# core.net
KiCad netlist of a schematic drawn in EAGLE
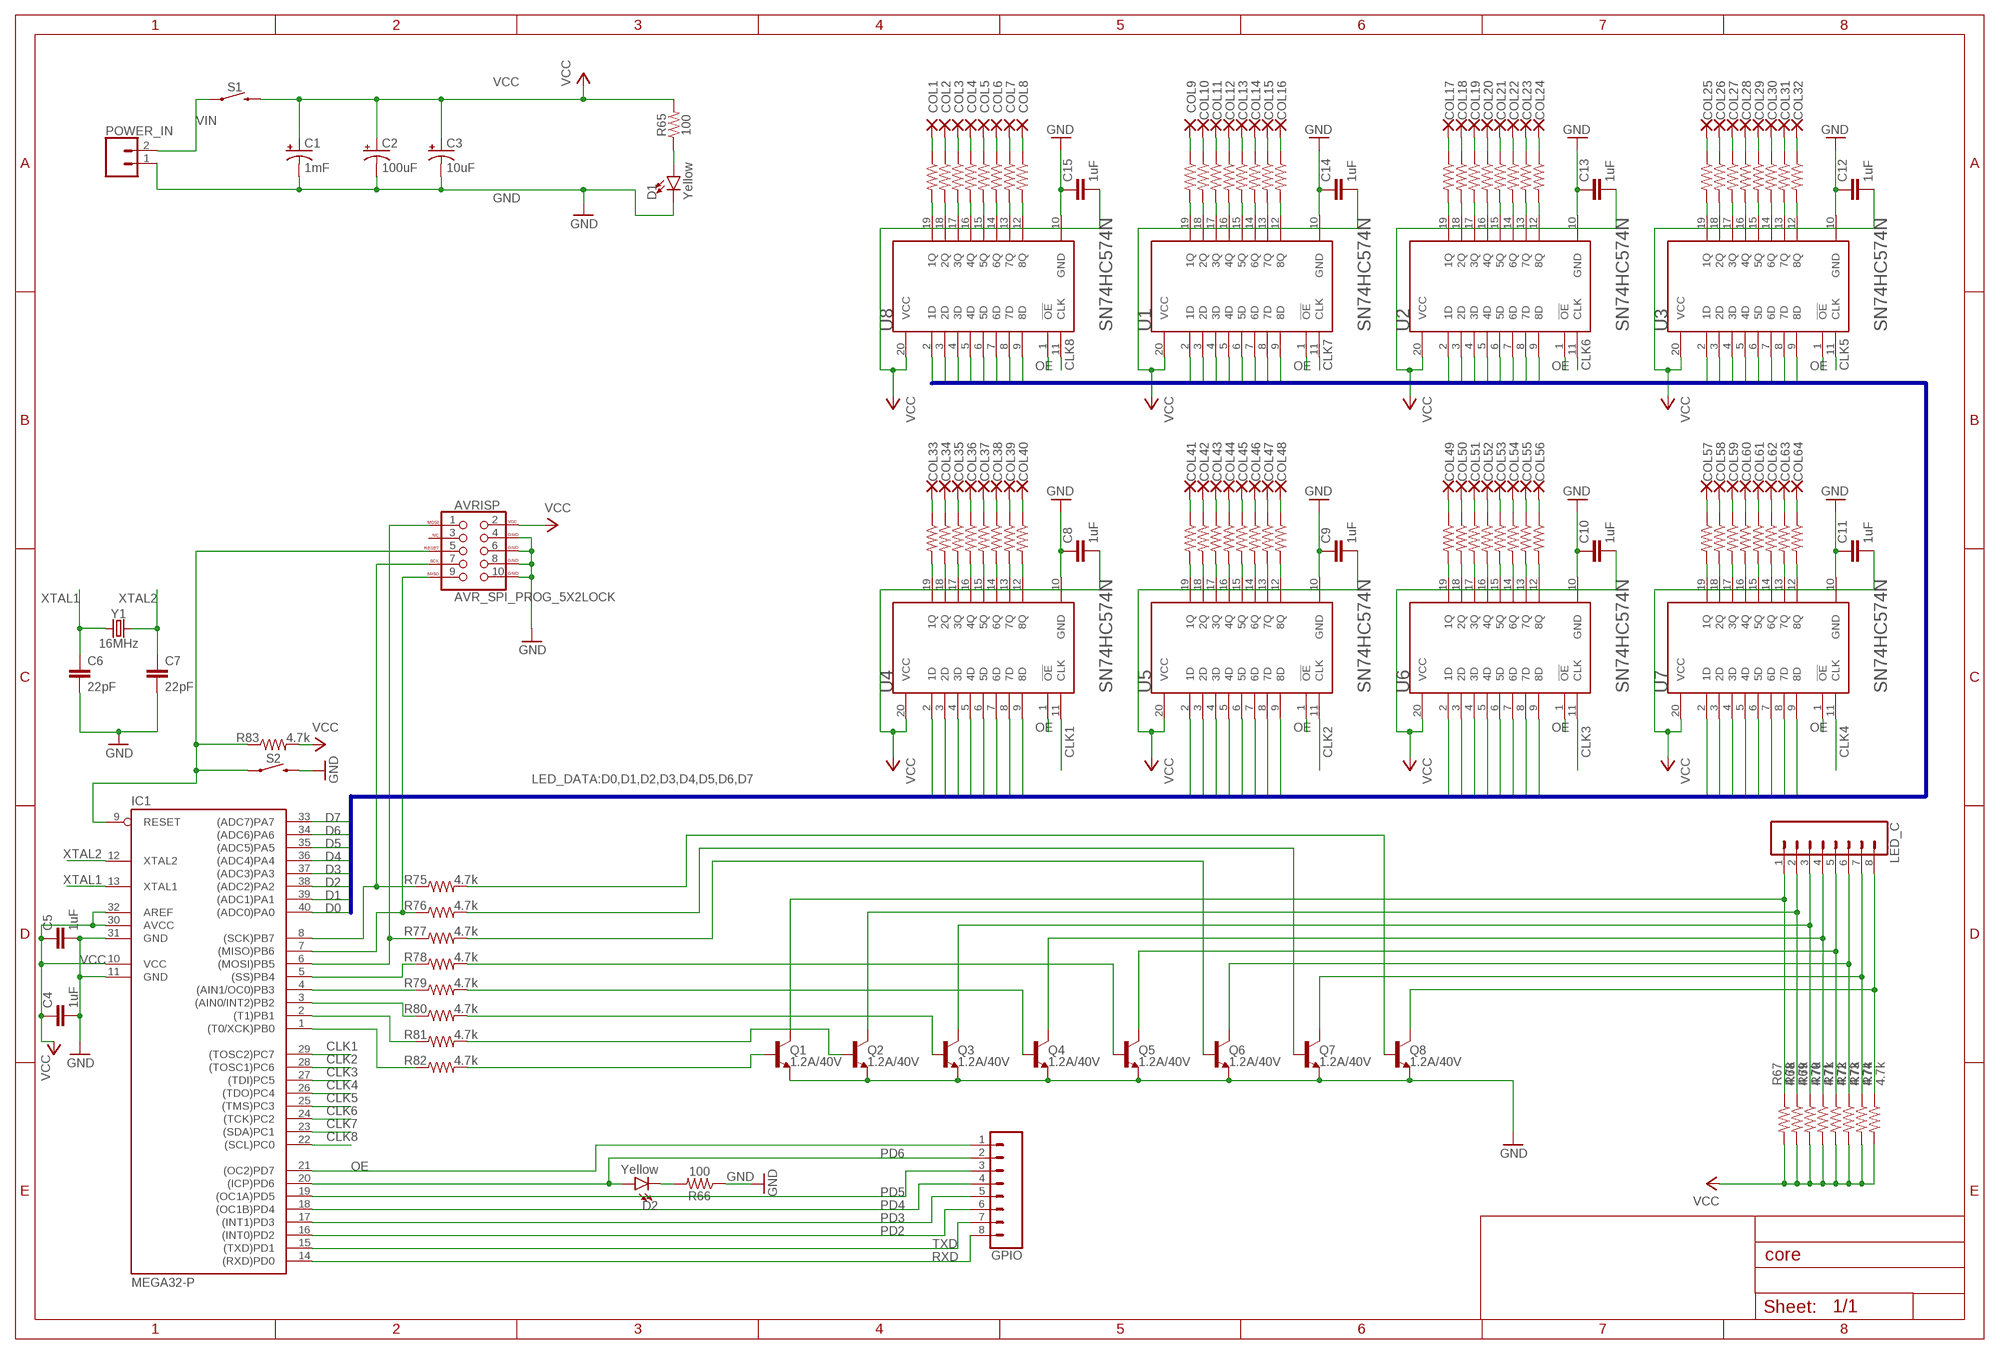
[diagram p0: schematic, sheet 1]

(export (version "E")
  (design (tool "Eeschema 10.0.6"))
  (components
    (comp (ref "AVRISP")
      (value "AVR_SPI_PROG_5X2LOCK")
      (footprint "eagle-import:2X5-SHROUDED_LOCK")
      (libsource (lib "eagle-import") (part "AVR_SPI_PROG_5X2LOCK"))
    )
    (comp (ref "C1")
      (value "1mF")
      (footprint "eagle-import:CPOL-RADIAL-5MM-10MM")
      (libsource (lib "eagle-import") (part "1000UF-RADIAL-5MM-25V-20%"))
    )
    (comp (ref "C2")
      (value "100uF")
      (footprint "eagle-import:CPOL-RADIAL-2.5MM-6.5MM")
      (libsource (lib "eagle-import") (part "100UF-POLAR-RADIAL-2.5MM-25V-20%"))
    )
    (comp (ref "C3")
      (value "10uF")
      (footprint "eagle-import:CPOL-RADIAL-2.5MM-5MM")
      (libsource (lib "eagle-import") (part "10UF-POLAR-RADIAL-2.5MM-25V-20%"))
    )
    (comp (ref "C4")
      (value "1uF")
      (footprint "eagle-import:C2.5-3")
      (libsource (lib "eagle-import") (part "C2,5-3"))
    )
    (comp (ref "C5")
      (value "1uF")
      (footprint "eagle-import:C2.5-3")
      (libsource (lib "eagle-import") (part "C2,5-3"))
    )
    (comp (ref "C6")
      (value "22pF")
      (footprint "eagle-import:CAP-PTH-2.54")
      (libsource (lib "eagle-import") (part "22PF-PTH-2.54MM-200V-5%"))
    )
    (comp (ref "C7")
      (value "22pF")
      (footprint "eagle-import:CAP-PTH-2.54")
      (libsource (lib "eagle-import") (part "22PF-PTH-2.54MM-200V-5%"))
    )
    (comp (ref "C8")
      (value "1uF")
      (footprint "eagle-import:C2.5-3")
      (libsource (lib "eagle-import") (part "C2,5-3"))
    )
    (comp (ref "C9")
      (value "1uF")
      (footprint "eagle-import:C2.5-3")
      (libsource (lib "eagle-import") (part "C2,5-3"))
    )
    (comp (ref "C10")
      (value "1uF")
      (footprint "eagle-import:C2.5-3")
      (libsource (lib "eagle-import") (part "C2,5-3"))
    )
    (comp (ref "C11")
      (value "1uF")
      (footprint "eagle-import:C2.5-3")
      (libsource (lib "eagle-import") (part "C2,5-3"))
    )
    (comp (ref "C12")
      (value "1uF")
      (footprint "eagle-import:C2.5-3")
      (libsource (lib "eagle-import") (part "C2,5-3"))
    )
    (comp (ref "C13")
      (value "1uF")
      (footprint "eagle-import:C2.5-3")
      (libsource (lib "eagle-import") (part "C2,5-3"))
    )
    (comp (ref "C14")
      (value "1uF")
      (footprint "eagle-import:C2.5-3")
      (libsource (lib "eagle-import") (part "C2,5-3"))
    )
    (comp (ref "C15")
      (value "1uF")
      (footprint "eagle-import:C2.5-3")
      (libsource (lib "eagle-import") (part "C2,5-3"))
    )
    (comp (ref "COL1")
      (value "1,6/0,9")
      (footprint "eagle-import:1,6_0,9")
      (libsource (lib "eagle-import") (part "1,6/0,9"))
    )
    (comp (ref "COL2")
      (value "1,6/0,9")
      (footprint "eagle-import:1,6_0,9")
      (libsource (lib "eagle-import") (part "1,6/0,9"))
    )
    (comp (ref "COL3")
      (value "1,6/0,9")
      (footprint "eagle-import:1,6_0,9")
      (libsource (lib "eagle-import") (part "1,6/0,9"))
    )
    (comp (ref "COL4")
      (value "1,6/0,9")
      (footprint "eagle-import:1,6_0,9")
      (libsource (lib "eagle-import") (part "1,6/0,9"))
    )
    (comp (ref "COL5")
      (value "1,6/0,9")
      (footprint "eagle-import:1,6_0,9")
      (libsource (lib "eagle-import") (part "1,6/0,9"))
    )
    (comp (ref "COL6")
      (value "1,6/0,9")
      (footprint "eagle-import:1,6_0,9")
      (libsource (lib "eagle-import") (part "1,6/0,9"))
    )
    (comp (ref "COL7")
      (value "1,6/0,9")
      (footprint "eagle-import:1,6_0,9")
      (libsource (lib "eagle-import") (part "1,6/0,9"))
    )
    (comp (ref "COL8")
      (value "1,6/0,9")
      (footprint "eagle-import:1,6_0,9")
      (libsource (lib "eagle-import") (part "1,6/0,9"))
    )
    (comp (ref "COL9")
      (value "1,6/0,9")
      (footprint "eagle-import:1,6_0,9")
      (libsource (lib "eagle-import") (part "1,6/0,9"))
    )
    (comp (ref "COL10")
      (value "1,6/0,9")
      (footprint "eagle-import:1,6_0,9")
      (libsource (lib "eagle-import") (part "1,6/0,9"))
    )
    (comp (ref "COL11")
      (value "1,6/0,9")
      (footprint "eagle-import:1,6_0,9")
      (libsource (lib "eagle-import") (part "1,6/0,9"))
    )
    (comp (ref "COL12")
      (value "1,6/0,9")
      (footprint "eagle-import:1,6_0,9")
      (libsource (lib "eagle-import") (part "1,6/0,9"))
    )
    (comp (ref "COL13")
      (value "1,6/0,9")
      (footprint "eagle-import:1,6_0,9")
      (libsource (lib "eagle-import") (part "1,6/0,9"))
    )
    (comp (ref "COL14")
      (value "1,6/0,9")
      (footprint "eagle-import:1,6_0,9")
      (libsource (lib "eagle-import") (part "1,6/0,9"))
    )
    (comp (ref "COL15")
      (value "1,6/0,9")
      (footprint "eagle-import:1,6_0,9")
      (libsource (lib "eagle-import") (part "1,6/0,9"))
    )
    (comp (ref "COL16")
      (value "1,6/0,9")
      (footprint "eagle-import:1,6_0,9")
      (libsource (lib "eagle-import") (part "1,6/0,9"))
    )
    (comp (ref "COL17")
      (value "1,6/0,9")
      (footprint "eagle-import:1,6_0,9")
      (libsource (lib "eagle-import") (part "1,6/0,9"))
    )
    (comp (ref "COL18")
      (value "1,6/0,9")
      (footprint "eagle-import:1,6_0,9")
      (libsource (lib "eagle-import") (part "1,6/0,9"))
    )
    (comp (ref "COL19")
      (value "1,6/0,9")
      (footprint "eagle-import:1,6_0,9")
      (libsource (lib "eagle-import") (part "1,6/0,9"))
    )
    (comp (ref "COL20")
      (value "1,6/0,9")
      (footprint "eagle-import:1,6_0,9")
      (libsource (lib "eagle-import") (part "1,6/0,9"))
    )
    (comp (ref "COL21")
      (value "1,6/0,9")
      (footprint "eagle-import:1,6_0,9")
      (libsource (lib "eagle-import") (part "1,6/0,9"))
    )
    (comp (ref "COL22")
      (value "1,6/0,9")
      (footprint "eagle-import:1,6_0,9")
      (libsource (lib "eagle-import") (part "1,6/0,9"))
    )
    (comp (ref "COL23")
      (value "1,6/0,9")
      (footprint "eagle-import:1,6_0,9")
      (libsource (lib "eagle-import") (part "1,6/0,9"))
    )
    (comp (ref "COL24")
      (value "1,6/0,9")
      (footprint "eagle-import:1,6_0,9")
      (libsource (lib "eagle-import") (part "1,6/0,9"))
    )
    (comp (ref "COL25")
      (value "1,6/0,9")
      (footprint "eagle-import:1,6_0,9")
      (libsource (lib "eagle-import") (part "1,6/0,9"))
    )
    (comp (ref "COL26")
      (value "1,6/0,9")
      (footprint "eagle-import:1,6_0,9")
      (libsource (lib "eagle-import") (part "1,6/0,9"))
    )
    (comp (ref "COL27")
      (value "1,6/0,9")
      (footprint "eagle-import:1,6_0,9")
      (libsource (lib "eagle-import") (part "1,6/0,9"))
    )
    (comp (ref "COL28")
      (value "1,6/0,9")
      (footprint "eagle-import:1,6_0,9")
      (libsource (lib "eagle-import") (part "1,6/0,9"))
    )
    (comp (ref "COL29")
      (value "1,6/0,9")
      (footprint "eagle-import:1,6_0,9")
      (libsource (lib "eagle-import") (part "1,6/0,9"))
    )
    (comp (ref "COL30")
      (value "1,6/0,9")
      (footprint "eagle-import:1,6_0,9")
      (libsource (lib "eagle-import") (part "1,6/0,9"))
    )
    (comp (ref "COL31")
      (value "1,6/0,9")
      (footprint "eagle-import:1,6_0,9")
      (libsource (lib "eagle-import") (part "1,6/0,9"))
    )
    (comp (ref "COL32")
      (value "1,6/0,9")
      (footprint "eagle-import:1,6_0,9")
      (libsource (lib "eagle-import") (part "1,6/0,9"))
    )
    (comp (ref "COL33")
      (value "1,6/0,9")
      (footprint "eagle-import:1,6_0,9")
      (libsource (lib "eagle-import") (part "1,6/0,9"))
    )
    (comp (ref "COL34")
      (value "1,6/0,9")
      (footprint "eagle-import:1,6_0,9")
      (libsource (lib "eagle-import") (part "1,6/0,9"))
    )
    (comp (ref "COL35")
      (value "1,6/0,9")
      (footprint "eagle-import:1,6_0,9")
      (libsource (lib "eagle-import") (part "1,6/0,9"))
    )
    (comp (ref "COL36")
      (value "1,6/0,9")
      (footprint "eagle-import:1,6_0,9")
      (libsource (lib "eagle-import") (part "1,6/0,9"))
    )
    (comp (ref "COL37")
      (value "1,6/0,9")
      (footprint "eagle-import:1,6_0,9")
      (libsource (lib "eagle-import") (part "1,6/0,9"))
    )
    (comp (ref "COL38")
      (value "1,6/0,9")
      (footprint "eagle-import:1,6_0,9")
      (libsource (lib "eagle-import") (part "1,6/0,9"))
    )
    (comp (ref "COL39")
      (value "1,6/0,9")
      (footprint "eagle-import:1,6_0,9")
      (libsource (lib "eagle-import") (part "1,6/0,9"))
    )
    (comp (ref "COL40")
      (value "1,6/0,9")
      (footprint "eagle-import:1,6_0,9")
      (libsource (lib "eagle-import") (part "1,6/0,9"))
    )
    (comp (ref "COL41")
      (value "1,6/0,9")
      (footprint "eagle-import:1,6_0,9")
      (libsource (lib "eagle-import") (part "1,6/0,9"))
    )
    (comp (ref "COL42")
      (value "1,6/0,9")
      (footprint "eagle-import:1,6_0,9")
      (libsource (lib "eagle-import") (part "1,6/0,9"))
    )
    (comp (ref "COL43")
      (value "1,6/0,9")
      (footprint "eagle-import:1,6_0,9")
      (libsource (lib "eagle-import") (part "1,6/0,9"))
    )
    (comp (ref "COL44")
      (value "1,6/0,9")
      (footprint "eagle-import:1,6_0,9")
      (libsource (lib "eagle-import") (part "1,6/0,9"))
    )
    (comp (ref "COL45")
      (value "1,6/0,9")
      (footprint "eagle-import:1,6_0,9")
      (libsource (lib "eagle-import") (part "1,6/0,9"))
    )
    (comp (ref "COL46")
      (value "1,6/0,9")
      (footprint "eagle-import:1,6_0,9")
      (libsource (lib "eagle-import") (part "1,6/0,9"))
    )
    (comp (ref "COL47")
      (value "1,6/0,9")
      (footprint "eagle-import:1,6_0,9")
      (libsource (lib "eagle-import") (part "1,6/0,9"))
    )
    (comp (ref "COL48")
      (value "1,6/0,9")
      (footprint "eagle-import:1,6_0,9")
      (libsource (lib "eagle-import") (part "1,6/0,9"))
    )
    (comp (ref "COL49")
      (value "1,6/0,9")
      (footprint "eagle-import:1,6_0,9")
      (libsource (lib "eagle-import") (part "1,6/0,9"))
    )
    (comp (ref "COL50")
      (value "1,6/0,9")
      (footprint "eagle-import:1,6_0,9")
      (libsource (lib "eagle-import") (part "1,6/0,9"))
    )
    (comp (ref "COL51")
      (value "1,6/0,9")
      (footprint "eagle-import:1,6_0,9")
      (libsource (lib "eagle-import") (part "1,6/0,9"))
    )
    (comp (ref "COL52")
      (value "1,6/0,9")
      (footprint "eagle-import:1,6_0,9")
      (libsource (lib "eagle-import") (part "1,6/0,9"))
    )
    (comp (ref "COL53")
      (value "1,6/0,9")
      (footprint "eagle-import:1,6_0,9")
      (libsource (lib "eagle-import") (part "1,6/0,9"))
    )
    (comp (ref "COL54")
      (value "1,6/0,9")
      (footprint "eagle-import:1,6_0,9")
      (libsource (lib "eagle-import") (part "1,6/0,9"))
    )
    (comp (ref "COL55")
      (value "1,6/0,9")
      (footprint "eagle-import:1,6_0,9")
      (libsource (lib "eagle-import") (part "1,6/0,9"))
    )
    (comp (ref "COL56")
      (value "1,6/0,9")
      (footprint "eagle-import:1,6_0,9")
      (libsource (lib "eagle-import") (part "1,6/0,9"))
    )
    (comp (ref "COL57")
      (value "1,6/0,9")
      (footprint "eagle-import:1,6_0,9")
      (libsource (lib "eagle-import") (part "1,6/0,9"))
    )
    (comp (ref "COL58")
      (value "1,6/0,9")
      (footprint "eagle-import:1,6_0,9")
      (libsource (lib "eagle-import") (part "1,6/0,9"))
    )
    (comp (ref "COL59")
      (value "1,6/0,9")
      (footprint "eagle-import:1,6_0,9")
      (libsource (lib "eagle-import") (part "1,6/0,9"))
    )
    (comp (ref "COL60")
      (value "1,6/0,9")
      (footprint "eagle-import:1,6_0,9")
      (libsource (lib "eagle-import") (part "1,6/0,9"))
    )
    (comp (ref "COL61")
      (value "1,6/0,9")
      (footprint "eagle-import:1,6_0,9")
      (libsource (lib "eagle-import") (part "1,6/0,9"))
    )
    (comp (ref "COL62")
      (value "1,6/0,9")
      (footprint "eagle-import:1,6_0,9")
      (libsource (lib "eagle-import") (part "1,6/0,9"))
    )
    (comp (ref "COL63")
      (value "1,6/0,9")
      (footprint "eagle-import:1,6_0,9")
      (libsource (lib "eagle-import") (part "1,6/0,9"))
    )
    (comp (ref "COL64")
      (value "1,6/0,9")
      (footprint "eagle-import:1,6_0,9")
      (libsource (lib "eagle-import") (part "1,6/0,9"))
    )
    (comp (ref "D1")
      (value "Yellow")
      (footprint "eagle-import:LED-1206")
      (libsource (lib "eagle-import") (part "LED-YELLOWLILYPAD"))
    )
    (comp (ref "D2")
      (value "Yellow")
      (footprint "eagle-import:LED-1206")
      (libsource (lib "eagle-import") (part "LED-YELLOWLILYPAD"))
    )
    (comp (ref "GPIO")
      (value "CONN_08\"")
      (footprint "eagle-import:1X08")
      (libsource (lib "eagle-import") (part "CONN_08{dblquote}"))
    )
    (comp (ref "IC1")
      (value "MEGA32-P")
      (footprint "eagle-import:DIL40")
      (fields (field (name "MPN") "ATMEGA32-16PU"))
      (libsource (lib "eagle-import") (part "MEGA32-P"))
    )
    (comp (ref "LED_C")
      (value "CONN_08\"")
      (footprint "eagle-import:1X08")
      (libsource (lib "eagle-import") (part "CONN_08{dblquote}"))
    )
    (comp (ref "POWER_IN")
      (value "CONN_02POLAR")
      (footprint "eagle-import:MOLEX-1X2")
      (libsource (lib "eagle-import") (part "CONN_02POLAR"))
    )
    (comp (ref "Q1")
      (value "1.2A/40V")
      (footprint "eagle-import:SOT23-3")
      (libsource (lib "eagle-import") (part "TRANS_NPN-MMBT2222AL"))
    )
    (comp (ref "Q2")
      (value "1.2A/40V")
      (footprint "eagle-import:SOT23-3")
      (libsource (lib "eagle-import") (part "TRANS_NPN-MMBT2222AL"))
    )
    (comp (ref "Q3")
      (value "1.2A/40V")
      (footprint "eagle-import:SOT23-3")
      (libsource (lib "eagle-import") (part "TRANS_NPN-MMBT2222AL"))
    )
    (comp (ref "Q4")
      (value "1.2A/40V")
      (footprint "eagle-import:SOT23-3")
      (libsource (lib "eagle-import") (part "TRANS_NPN-MMBT2222AL"))
    )
    (comp (ref "Q5")
      (value "1.2A/40V")
      (footprint "eagle-import:SOT23-3")
      (libsource (lib "eagle-import") (part "TRANS_NPN-MMBT2222AL"))
    )
    (comp (ref "Q6")
      (value "1.2A/40V")
      (footprint "eagle-import:SOT23-3")
      (libsource (lib "eagle-import") (part "TRANS_NPN-MMBT2222AL"))
    )
    (comp (ref "Q7")
      (value "1.2A/40V")
      (footprint "eagle-import:SOT23-3")
      (libsource (lib "eagle-import") (part "TRANS_NPN-MMBT2222AL"))
    )
    (comp (ref "Q8")
      (value "1.2A/40V")
      (footprint "eagle-import:SOT23-3")
      (libsource (lib "eagle-import") (part "TRANS_NPN-MMBT2222AL"))
    )
    (comp (ref "R1")
      (value "100")
      (footprint "eagle-import:AXIAL-0.3")
      (libsource (lib "eagle-import") (part "100OHM-HORIZ-1/4W-1%"))
    )
    (comp (ref "R2")
      (value "100")
      (footprint "eagle-import:AXIAL-0.3")
      (libsource (lib "eagle-import") (part "100OHM-HORIZ-1/4W-1%"))
    )
    (comp (ref "R3")
      (value "100")
      (footprint "eagle-import:AXIAL-0.3")
      (libsource (lib "eagle-import") (part "100OHM-HORIZ-1/4W-1%"))
    )
    (comp (ref "R4")
      (value "100")
      (footprint "eagle-import:AXIAL-0.3")
      (libsource (lib "eagle-import") (part "100OHM-HORIZ-1/4W-1%"))
    )
    (comp (ref "R5")
      (value "100")
      (footprint "eagle-import:AXIAL-0.3")
      (libsource (lib "eagle-import") (part "100OHM-HORIZ-1/4W-1%"))
    )
    (comp (ref "R6")
      (value "100")
      (footprint "eagle-import:AXIAL-0.3")
      (libsource (lib "eagle-import") (part "100OHM-HORIZ-1/4W-1%"))
    )
    (comp (ref "R7")
      (value "100")
      (footprint "eagle-import:AXIAL-0.3")
      (libsource (lib "eagle-import") (part "100OHM-HORIZ-1/4W-1%"))
    )
    (comp (ref "R8")
      (value "100")
      (footprint "eagle-import:AXIAL-0.3")
      (libsource (lib "eagle-import") (part "100OHM-HORIZ-1/4W-1%"))
    )
    (comp (ref "R9")
      (value "100")
      (footprint "eagle-import:AXIAL-0.3")
      (libsource (lib "eagle-import") (part "100OHM-HORIZ-1/4W-1%"))
    )
    (comp (ref "R10")
      (value "100")
      (footprint "eagle-import:AXIAL-0.3")
      (libsource (lib "eagle-import") (part "100OHM-HORIZ-1/4W-1%"))
    )
    (comp (ref "R11")
      (value "100")
      (footprint "eagle-import:AXIAL-0.3")
      (libsource (lib "eagle-import") (part "100OHM-HORIZ-1/4W-1%"))
    )
    (comp (ref "R12")
      (value "100")
      (footprint "eagle-import:AXIAL-0.3")
      (libsource (lib "eagle-import") (part "100OHM-HORIZ-1/4W-1%"))
    )
    (comp (ref "R13")
      (value "100")
      (footprint "eagle-import:AXIAL-0.3")
      (libsource (lib "eagle-import") (part "100OHM-HORIZ-1/4W-1%"))
    )
    (comp (ref "R14")
      (value "100")
      (footprint "eagle-import:AXIAL-0.3")
      (libsource (lib "eagle-import") (part "100OHM-HORIZ-1/4W-1%"))
    )
    (comp (ref "R15")
      (value "100")
      (footprint "eagle-import:AXIAL-0.3")
      (libsource (lib "eagle-import") (part "100OHM-HORIZ-1/4W-1%"))
    )
    (comp (ref "R16")
      (value "100")
      (footprint "eagle-import:AXIAL-0.3")
      (libsource (lib "eagle-import") (part "100OHM-HORIZ-1/4W-1%"))
    )
    (comp (ref "R17")
      (value "100")
      (footprint "eagle-import:AXIAL-0.3")
      (libsource (lib "eagle-import") (part "100OHM-HORIZ-1/4W-1%"))
    )
    (comp (ref "R18")
      (value "100")
      (footprint "eagle-import:AXIAL-0.3")
      (libsource (lib "eagle-import") (part "100OHM-HORIZ-1/4W-1%"))
    )
    (comp (ref "R19")
      (value "100")
      (footprint "eagle-import:AXIAL-0.3")
      (libsource (lib "eagle-import") (part "100OHM-HORIZ-1/4W-1%"))
    )
    (comp (ref "R20")
      (value "100")
      (footprint "eagle-import:AXIAL-0.3")
      (libsource (lib "eagle-import") (part "100OHM-HORIZ-1/4W-1%"))
    )
    (comp (ref "R21")
      (value "100")
      (footprint "eagle-import:AXIAL-0.3")
      (libsource (lib "eagle-import") (part "100OHM-HORIZ-1/4W-1%"))
    )
    (comp (ref "R22")
      (value "100")
      (footprint "eagle-import:AXIAL-0.3")
      (libsource (lib "eagle-import") (part "100OHM-HORIZ-1/4W-1%"))
    )
    (comp (ref "R23")
      (value "100")
      (footprint "eagle-import:AXIAL-0.3")
      (libsource (lib "eagle-import") (part "100OHM-HORIZ-1/4W-1%"))
    )
    (comp (ref "R24")
      (value "100")
      (footprint "eagle-import:AXIAL-0.3")
      (libsource (lib "eagle-import") (part "100OHM-HORIZ-1/4W-1%"))
    )
    (comp (ref "R25")
      (value "100")
      (footprint "eagle-import:AXIAL-0.3")
      (libsource (lib "eagle-import") (part "100OHM-HORIZ-1/4W-1%"))
    )
    (comp (ref "R26")
      (value "100")
      (footprint "eagle-import:AXIAL-0.3")
      (libsource (lib "eagle-import") (part "100OHM-HORIZ-1/4W-1%"))
    )
    (comp (ref "R27")
      (value "100")
      (footprint "eagle-import:AXIAL-0.3")
      (libsource (lib "eagle-import") (part "100OHM-HORIZ-1/4W-1%"))
    )
    (comp (ref "R28")
      (value "100")
      (footprint "eagle-import:AXIAL-0.3")
      (libsource (lib "eagle-import") (part "100OHM-HORIZ-1/4W-1%"))
    )
    (comp (ref "R29")
      (value "100")
      (footprint "eagle-import:AXIAL-0.3")
      (libsource (lib "eagle-import") (part "100OHM-HORIZ-1/4W-1%"))
    )
    (comp (ref "R30")
      (value "100")
      (footprint "eagle-import:AXIAL-0.3")
      (libsource (lib "eagle-import") (part "100OHM-HORIZ-1/4W-1%"))
    )
    (comp (ref "R31")
      (value "100")
      (footprint "eagle-import:AXIAL-0.3")
      (libsource (lib "eagle-import") (part "100OHM-HORIZ-1/4W-1%"))
    )
    (comp (ref "R32")
      (value "100")
      (footprint "eagle-import:AXIAL-0.3")
      (libsource (lib "eagle-import") (part "100OHM-HORIZ-1/4W-1%"))
    )
    (comp (ref "R33")
      (value "100")
      (footprint "eagle-import:AXIAL-0.3")
      (libsource (lib "eagle-import") (part "100OHM-HORIZ-1/4W-1%"))
    )
    (comp (ref "R34")
      (value "100")
      (footprint "eagle-import:AXIAL-0.3")
      (libsource (lib "eagle-import") (part "100OHM-HORIZ-1/4W-1%"))
    )
    (comp (ref "R35")
      (value "100")
      (footprint "eagle-import:AXIAL-0.3")
      (libsource (lib "eagle-import") (part "100OHM-HORIZ-1/4W-1%"))
    )
    (comp (ref "R36")
      (value "100")
      (footprint "eagle-import:AXIAL-0.3")
      (libsource (lib "eagle-import") (part "100OHM-HORIZ-1/4W-1%"))
    )
    (comp (ref "R37")
      (value "100")
      (footprint "eagle-import:AXIAL-0.3")
      (libsource (lib "eagle-import") (part "100OHM-HORIZ-1/4W-1%"))
    )
    (comp (ref "R38")
      (value "100")
      (footprint "eagle-import:AXIAL-0.3")
      (libsource (lib "eagle-import") (part "100OHM-HORIZ-1/4W-1%"))
    )
    (comp (ref "R39")
      (value "100")
      (footprint "eagle-import:AXIAL-0.3")
      (libsource (lib "eagle-import") (part "100OHM-HORIZ-1/4W-1%"))
    )
    (comp (ref "R40")
      (value "100")
      (footprint "eagle-import:AXIAL-0.3")
      (libsource (lib "eagle-import") (part "100OHM-HORIZ-1/4W-1%"))
    )
    (comp (ref "R41")
      (value "100")
      (footprint "eagle-import:AXIAL-0.3")
      (libsource (lib "eagle-import") (part "100OHM-HORIZ-1/4W-1%"))
    )
    (comp (ref "R42")
      (value "100")
      (footprint "eagle-import:AXIAL-0.3")
      (libsource (lib "eagle-import") (part "100OHM-HORIZ-1/4W-1%"))
    )
    (comp (ref "R43")
      (value "100")
      (footprint "eagle-import:AXIAL-0.3")
      (libsource (lib "eagle-import") (part "100OHM-HORIZ-1/4W-1%"))
    )
    (comp (ref "R44")
      (value "100")
      (footprint "eagle-import:AXIAL-0.3")
      (libsource (lib "eagle-import") (part "100OHM-HORIZ-1/4W-1%"))
    )
    (comp (ref "R45")
      (value "100")
      (footprint "eagle-import:AXIAL-0.3")
      (libsource (lib "eagle-import") (part "100OHM-HORIZ-1/4W-1%"))
    )
    (comp (ref "R46")
      (value "100")
      (footprint "eagle-import:AXIAL-0.3")
      (libsource (lib "eagle-import") (part "100OHM-HORIZ-1/4W-1%"))
    )
    (comp (ref "R47")
      (value "100")
      (footprint "eagle-import:AXIAL-0.3")
      (libsource (lib "eagle-import") (part "100OHM-HORIZ-1/4W-1%"))
    )
    (comp (ref "R48")
      (value "100")
      (footprint "eagle-import:AXIAL-0.3")
      (libsource (lib "eagle-import") (part "100OHM-HORIZ-1/4W-1%"))
    )
    (comp (ref "R49")
      (value "100")
      (footprint "eagle-import:AXIAL-0.3")
      (libsource (lib "eagle-import") (part "100OHM-HORIZ-1/4W-1%"))
    )
    (comp (ref "R50")
      (value "100")
      (footprint "eagle-import:AXIAL-0.3")
      (libsource (lib "eagle-import") (part "100OHM-HORIZ-1/4W-1%"))
    )
    (comp (ref "R51")
      (value "100")
      (footprint "eagle-import:AXIAL-0.3")
      (libsource (lib "eagle-import") (part "100OHM-HORIZ-1/4W-1%"))
    )
    (comp (ref "R52")
      (value "100")
      (footprint "eagle-import:AXIAL-0.3")
      (libsource (lib "eagle-import") (part "100OHM-HORIZ-1/4W-1%"))
    )
    (comp (ref "R53")
      (value "100")
      (footprint "eagle-import:AXIAL-0.3")
      (libsource (lib "eagle-import") (part "100OHM-HORIZ-1/4W-1%"))
    )
    (comp (ref "R54")
      (value "100")
      (footprint "eagle-import:AXIAL-0.3")
      (libsource (lib "eagle-import") (part "100OHM-HORIZ-1/4W-1%"))
    )
    (comp (ref "R55")
      (value "100")
      (footprint "eagle-import:AXIAL-0.3")
      (libsource (lib "eagle-import") (part "100OHM-HORIZ-1/4W-1%"))
    )
    (comp (ref "R56")
      (value "100")
      (footprint "eagle-import:AXIAL-0.3")
      (libsource (lib "eagle-import") (part "100OHM-HORIZ-1/4W-1%"))
    )
    (comp (ref "R57")
      (value "100")
      (footprint "eagle-import:AXIAL-0.3")
      (libsource (lib "eagle-import") (part "100OHM-HORIZ-1/4W-1%"))
    )
    (comp (ref "R58")
      (value "100")
      (footprint "eagle-import:AXIAL-0.3")
      (libsource (lib "eagle-import") (part "100OHM-HORIZ-1/4W-1%"))
    )
    (comp (ref "R59")
      (value "100")
      (footprint "eagle-import:AXIAL-0.3")
      (libsource (lib "eagle-import") (part "100OHM-HORIZ-1/4W-1%"))
    )
    (comp (ref "R60")
      (value "100")
      (footprint "eagle-import:AXIAL-0.3")
      (libsource (lib "eagle-import") (part "100OHM-HORIZ-1/4W-1%"))
    )
    (comp (ref "R61")
      (value "100")
      (footprint "eagle-import:AXIAL-0.3")
      (libsource (lib "eagle-import") (part "100OHM-HORIZ-1/4W-1%"))
    )
    (comp (ref "R62")
      (value "100")
      (footprint "eagle-import:AXIAL-0.3")
      (libsource (lib "eagle-import") (part "100OHM-HORIZ-1/4W-1%"))
    )
    (comp (ref "R63")
      (value "100")
      (footprint "eagle-import:AXIAL-0.3")
      (libsource (lib "eagle-import") (part "100OHM-HORIZ-1/4W-1%"))
    )
    (comp (ref "R64")
      (value "100")
      (footprint "eagle-import:AXIAL-0.3")
      (libsource (lib "eagle-import") (part "100OHM-HORIZ-1/4W-1%"))
    )
    (comp (ref "R65")
      (value "100")
      (footprint "eagle-import:AXIAL-0.3")
      (libsource (lib "eagle-import") (part "100OHM-HORIZ-1/4W-1%"))
    )
    (comp (ref "R66")
      (value "100")
      (footprint "eagle-import:AXIAL-0.3")
      (libsource (lib "eagle-import") (part "100OHM-HORIZ-1/4W-1%"))
    )
    (comp (ref "R67")
      (value "4.7k")
      (footprint "eagle-import:AXIAL-0.3")
      (libsource (lib "eagle-import") (part "1KOHM-HORIZ-1/4W-1%"))
    )
    (comp (ref "R68")
      (value "4.7k")
      (footprint "eagle-import:AXIAL-0.3")
      (libsource (lib "eagle-import") (part "1KOHM-HORIZ-1/4W-1%"))
    )
    (comp (ref "R69")
      (value "4.7k")
      (footprint "eagle-import:AXIAL-0.3")
      (libsource (lib "eagle-import") (part "1KOHM-HORIZ-1/4W-1%"))
    )
    (comp (ref "R70")
      (value "4.7k")
      (footprint "eagle-import:AXIAL-0.3")
      (libsource (lib "eagle-import") (part "1KOHM-HORIZ-1/4W-1%"))
    )
    (comp (ref "R71")
      (value "4.7k")
      (footprint "eagle-import:AXIAL-0.3")
      (libsource (lib "eagle-import") (part "1KOHM-HORIZ-1/4W-1%"))
    )
    (comp (ref "R72")
      (value "4.7k")
      (footprint "eagle-import:AXIAL-0.3")
      (libsource (lib "eagle-import") (part "1KOHM-HORIZ-1/4W-1%"))
    )
    (comp (ref "R73")
      (value "4.7k")
      (footprint "eagle-import:AXIAL-0.3")
      (libsource (lib "eagle-import") (part "1KOHM-HORIZ-1/4W-1%"))
    )
    (comp (ref "R74")
      (value "4.7k")
      (footprint "eagle-import:AXIAL-0.3")
      (libsource (lib "eagle-import") (part "1KOHM-HORIZ-1/4W-1%"))
    )
    (comp (ref "R75")
      (value "4.7k")
      (footprint "eagle-import:AXIAL-0.3")
      (libsource (lib "eagle-import") (part "1KOHM-HORIZ-1/4W-1%"))
    )
    (comp (ref "R76")
      (value "4.7k")
      (footprint "eagle-import:AXIAL-0.3")
      (libsource (lib "eagle-import") (part "1KOHM-HORIZ-1/4W-1%"))
    )
    (comp (ref "R77")
      (value "4.7k")
      (footprint "eagle-import:AXIAL-0.3")
      (libsource (lib "eagle-import") (part "1KOHM-HORIZ-1/4W-1%"))
    )
    (comp (ref "R78")
      (value "4.7k")
      (footprint "eagle-import:AXIAL-0.3")
      (libsource (lib "eagle-import") (part "1KOHM-HORIZ-1/4W-1%"))
    )
    (comp (ref "R79")
      (value "4.7k")
      (footprint "eagle-import:AXIAL-0.3")
      (libsource (lib "eagle-import") (part "1KOHM-HORIZ-1/4W-1%"))
    )
    (comp (ref "R80")
      (value "4.7k")
      (footprint "eagle-import:AXIAL-0.3")
      (libsource (lib "eagle-import") (part "1KOHM-HORIZ-1/4W-1%"))
    )
    (comp (ref "R81")
      (value "4.7k")
      (footprint "eagle-import:AXIAL-0.3")
      (libsource (lib "eagle-import") (part "1KOHM-HORIZ-1/4W-1%"))
    )
    (comp (ref "R82")
      (value "4.7k")
      (footprint "eagle-import:AXIAL-0.3")
      (libsource (lib "eagle-import") (part "1KOHM-HORIZ-1/4W-1%"))
    )
    (comp (ref "R83")
      (value "4.7k")
      (footprint "eagle-import:AXIAL-0.3")
      (libsource (lib "eagle-import") (part "1KOHM-HORIZ-1/4W-1%"))
    )
    (comp (ref "S1")
      (value "MOMENTARY-SWITCH-SPST-PTH-RIGHT-ANGLE-KIT")
      (footprint "eagle-import:TACTILE_SWITCH_PTH_RIGHT_ANGLE_KIT")
      (libsource (lib "eagle-import") (part "MOMENTARY-SWITCH-SPST-PTH-RIGHT-ANGLE-KIT"))
    )
    (comp (ref "S2")
      (value "MOMENTARY-SWITCH-SPST-PTH-6.0MM")
      (footprint "eagle-import:TACTILE_SWITCH_PTH_6.0MM")
      (libsource (lib "eagle-import") (part "MOMENTARY-SWITCH-SPST-PTH-6.0MM"))
    )
    (comp (ref "U1")
      (value "TEXAS_INSTRUMENTS_SN74HC574NTEXAS_INSTRUMENTS_SN74HC574N_0_0")
      (footprint "eagle-import:TEXAS_INSTRUMENTS_SN74HC574N_0")
      (fields
        (field (name "DIGIKEY_PART_NUMBER") "296-1598-5-ND")
        (field (name "MF") "Texas Instruments")
        (field (name "MOUSER_PART_NUMBER") "595-SN74HC574N")
      )
      (libsource (lib "eagle-import") (part "TEXAS_INSTRUMENTS_SN74HC574NTEXAS_INSTRUMENTS_SN74HC574N_0_0"))
    )
    (comp (ref "U2")
      (value "TEXAS_INSTRUMENTS_SN74HC574NTEXAS_INSTRUMENTS_SN74HC574N_0_0")
      (footprint "eagle-import:TEXAS_INSTRUMENTS_SN74HC574N_0")
      (fields
        (field (name "DIGIKEY_PART_NUMBER") "296-1598-5-ND")
        (field (name "MF") "Texas Instruments")
        (field (name "MOUSER_PART_NUMBER") "595-SN74HC574N")
      )
      (libsource (lib "eagle-import") (part "TEXAS_INSTRUMENTS_SN74HC574NTEXAS_INSTRUMENTS_SN74HC574N_0_0"))
    )
    (comp (ref "U3")
      (value "TEXAS_INSTRUMENTS_SN74HC574NTEXAS_INSTRUMENTS_SN74HC574N_0_0")
      (footprint "eagle-import:TEXAS_INSTRUMENTS_SN74HC574N_0")
      (fields
        (field (name "DIGIKEY_PART_NUMBER") "296-1598-5-ND")
        (field (name "MF") "Texas Instruments")
        (field (name "MOUSER_PART_NUMBER") "595-SN74HC574N")
      )
      (libsource (lib "eagle-import") (part "TEXAS_INSTRUMENTS_SN74HC574NTEXAS_INSTRUMENTS_SN74HC574N_0_0"))
    )
    (comp (ref "U4")
      (value "TEXAS_INSTRUMENTS_SN74HC574NTEXAS_INSTRUMENTS_SN74HC574N_0_0")
      (footprint "eagle-import:TEXAS_INSTRUMENTS_SN74HC574N_0")
      (fields
        (field (name "DIGIKEY_PART_NUMBER") "296-1598-5-ND")
        (field (name "MF") "Texas Instruments")
        (field (name "MOUSER_PART_NUMBER") "595-SN74HC574N")
      )
      (libsource (lib "eagle-import") (part "TEXAS_INSTRUMENTS_SN74HC574NTEXAS_INSTRUMENTS_SN74HC574N_0_0"))
    )
    (comp (ref "U5")
      (value "TEXAS_INSTRUMENTS_SN74HC574NTEXAS_INSTRUMENTS_SN74HC574N_0_0")
      (footprint "eagle-import:TEXAS_INSTRUMENTS_SN74HC574N_0")
      (fields
        (field (name "DIGIKEY_PART_NUMBER") "296-1598-5-ND")
        (field (name "MF") "Texas Instruments")
        (field (name "MOUSER_PART_NUMBER") "595-SN74HC574N")
      )
      (libsource (lib "eagle-import") (part "TEXAS_INSTRUMENTS_SN74HC574NTEXAS_INSTRUMENTS_SN74HC574N_0_0"))
    )
    (comp (ref "U6")
      (value "TEXAS_INSTRUMENTS_SN74HC574NTEXAS_INSTRUMENTS_SN74HC574N_0_0")
      (footprint "eagle-import:TEXAS_INSTRUMENTS_SN74HC574N_0")
      (fields
        (field (name "DIGIKEY_PART_NUMBER") "296-1598-5-ND")
        (field (name "MF") "Texas Instruments")
        (field (name "MOUSER_PART_NUMBER") "595-SN74HC574N")
      )
      (libsource (lib "eagle-import") (part "TEXAS_INSTRUMENTS_SN74HC574NTEXAS_INSTRUMENTS_SN74HC574N_0_0"))
    )
    (comp (ref "U7")
      (value "TEXAS_INSTRUMENTS_SN74HC574NTEXAS_INSTRUMENTS_SN74HC574N_0_0")
      (footprint "eagle-import:TEXAS_INSTRUMENTS_SN74HC574N_0")
      (fields
        (field (name "DIGIKEY_PART_NUMBER") "296-1598-5-ND")
        (field (name "MF") "Texas Instruments")
        (field (name "MOUSER_PART_NUMBER") "595-SN74HC574N")
      )
      (libsource (lib "eagle-import") (part "TEXAS_INSTRUMENTS_SN74HC574NTEXAS_INSTRUMENTS_SN74HC574N_0_0"))
    )
    (comp (ref "U8")
      (value "TEXAS_INSTRUMENTS_SN74HC574NTEXAS_INSTRUMENTS_SN74HC574N_0_0")
      (footprint "eagle-import:TEXAS_INSTRUMENTS_SN74HC574N_0")
      (fields
        (field (name "DIGIKEY_PART_NUMBER") "296-1598-5-ND")
        (field (name "MF") "Texas Instruments")
        (field (name "MOUSER_PART_NUMBER") "595-SN74HC574N")
      )
      (libsource (lib "eagle-import") (part "TEXAS_INSTRUMENTS_SN74HC574NTEXAS_INSTRUMENTS_SN74HC574N_0_0"))
    )
    (comp (ref "Y1")
      (value "16MHz")
      (footprint "eagle-import:HC49US")
      (libsource (lib "eagle-import") (part "CRYSTAL-16MHZPTH-HC49US"))
    )
  )
  (nets
    (net (code "2") (name "/CLK1") (class "Default")
      (node (ref "IC1") (pin "29") (pinfunction "(TOSC2)PC7_29") (pintype "bidirectional"))
      (node (ref "U4") (pin "11") (pinfunction "CLK_11") (pintype "input"))
    )
    (net (code "3") (name "/CLK2") (class "Default")
      (node (ref "IC1") (pin "28") (pinfunction "(TOSC1)PC6_28") (pintype "bidirectional"))
      (node (ref "U5") (pin "11") (pinfunction "CLK_11") (pintype "input"))
    )
    (net (code "4") (name "/CLK3") (class "Default")
      (node (ref "IC1") (pin "27") (pinfunction "(TDI)PC5_27") (pintype "bidirectional"))
      (node (ref "U6") (pin "11") (pinfunction "CLK_11") (pintype "input"))
    )
    (net (code "5") (name "/CLK4") (class "Default")
      (node (ref "IC1") (pin "26") (pinfunction "(TDO)PC4_26") (pintype "bidirectional"))
      (node (ref "U7") (pin "11") (pinfunction "CLK_11") (pintype "input"))
    )
    (net (code "6") (name "/CLK5") (class "Default")
      (node (ref "IC1") (pin "25") (pinfunction "(TMS)PC3_25") (pintype "bidirectional"))
      (node (ref "U3") (pin "11") (pinfunction "CLK_11") (pintype "input"))
    )
    (net (code "7") (name "/CLK6") (class "Default")
      (node (ref "IC1") (pin "24") (pinfunction "(TCK)PC2_24") (pintype "bidirectional"))
      (node (ref "U2") (pin "11") (pinfunction "CLK_11") (pintype "input"))
    )
    (net (code "8") (name "/CLK7") (class "Default")
      (node (ref "IC1") (pin "23") (pinfunction "(SDA)PC1_23") (pintype "bidirectional"))
      (node (ref "U1") (pin "11") (pinfunction "CLK_11") (pintype "input"))
    )
    (net (code "9") (name "/CLK8") (class "Default")
      (node (ref "IC1") (pin "22") (pinfunction "(SCL)PC0_22") (pintype "bidirectional"))
      (node (ref "U8") (pin "11") (pinfunction "CLK_11") (pintype "input"))
    )
    (net (code "10") (name "/D0") (class "Default")
      (node (ref "IC1") (pin "40") (pinfunction "(ADC0)PA0_40") (pintype "bidirectional"))
      (node (ref "U1") (pin "2") (pinfunction "1D_2") (pintype "input"))
      (node (ref "U2") (pin "2") (pinfunction "1D_2") (pintype "input"))
      (node (ref "U3") (pin "2") (pinfunction "1D_2") (pintype "input"))
      (node (ref "U4") (pin "2") (pinfunction "1D_2") (pintype "input"))
      (node (ref "U5") (pin "2") (pinfunction "1D_2") (pintype "input"))
      (node (ref "U6") (pin "2") (pinfunction "1D_2") (pintype "input"))
      (node (ref "U7") (pin "2") (pinfunction "1D_2") (pintype "input"))
      (node (ref "U8") (pin "2") (pinfunction "1D_2") (pintype "input"))
    )
    (net (code "11") (name "/D1") (class "Default")
      (node (ref "IC1") (pin "39") (pinfunction "(ADC1)PA1_39") (pintype "bidirectional"))
      (node (ref "U1") (pin "3") (pinfunction "2D_3") (pintype "input"))
      (node (ref "U2") (pin "3") (pinfunction "2D_3") (pintype "input"))
      (node (ref "U3") (pin "3") (pinfunction "2D_3") (pintype "input"))
      (node (ref "U4") (pin "3") (pinfunction "2D_3") (pintype "input"))
      (node (ref "U5") (pin "3") (pinfunction "2D_3") (pintype "input"))
      (node (ref "U6") (pin "3") (pinfunction "2D_3") (pintype "input"))
      (node (ref "U7") (pin "3") (pinfunction "2D_3") (pintype "input"))
      (node (ref "U8") (pin "3") (pinfunction "2D_3") (pintype "input"))
    )
    (net (code "12") (name "/D2") (class "Default")
      (node (ref "IC1") (pin "38") (pinfunction "(ADC2)PA2_38") (pintype "bidirectional"))
      (node (ref "U1") (pin "4") (pinfunction "3D_4") (pintype "input"))
      (node (ref "U2") (pin "4") (pinfunction "3D_4") (pintype "input"))
      (node (ref "U3") (pin "4") (pinfunction "3D_4") (pintype "input"))
      (node (ref "U4") (pin "4") (pinfunction "3D_4") (pintype "input"))
      (node (ref "U5") (pin "4") (pinfunction "3D_4") (pintype "input"))
      (node (ref "U6") (pin "4") (pinfunction "3D_4") (pintype "input"))
      (node (ref "U7") (pin "4") (pinfunction "3D_4") (pintype "input"))
      (node (ref "U8") (pin "4") (pinfunction "3D_4") (pintype "input"))
    )
    (net (code "13") (name "/D3") (class "Default")
      (node (ref "IC1") (pin "37") (pinfunction "(ADC3)PA3_37") (pintype "bidirectional"))
      (node (ref "U1") (pin "5") (pinfunction "4D_5") (pintype "input"))
      (node (ref "U2") (pin "5") (pinfunction "4D_5") (pintype "input"))
      (node (ref "U3") (pin "5") (pinfunction "4D_5") (pintype "input"))
      (node (ref "U4") (pin "5") (pinfunction "4D_5") (pintype "input"))
      (node (ref "U5") (pin "5") (pinfunction "4D_5") (pintype "input"))
      (node (ref "U6") (pin "5") (pinfunction "4D_5") (pintype "input"))
      (node (ref "U7") (pin "5") (pinfunction "4D_5") (pintype "input"))
      (node (ref "U8") (pin "5") (pinfunction "4D_5") (pintype "input"))
    )
    (net (code "14") (name "/D4") (class "Default")
      (node (ref "IC1") (pin "36") (pinfunction "(ADC4)PA4_36") (pintype "bidirectional"))
      (node (ref "U1") (pin "6") (pinfunction "5D_6") (pintype "input"))
      (node (ref "U2") (pin "6") (pinfunction "5D_6") (pintype "input"))
      (node (ref "U3") (pin "6") (pinfunction "5D_6") (pintype "input"))
      (node (ref "U4") (pin "6") (pinfunction "5D_6") (pintype "input"))
      (node (ref "U5") (pin "6") (pinfunction "5D_6") (pintype "input"))
      (node (ref "U6") (pin "6") (pinfunction "5D_6") (pintype "input"))
      (node (ref "U7") (pin "6") (pinfunction "5D_6") (pintype "input"))
      (node (ref "U8") (pin "6") (pinfunction "5D_6") (pintype "input"))
    )
    (net (code "15") (name "/D5") (class "Default")
      (node (ref "IC1") (pin "35") (pinfunction "(ADC5)PA5_35") (pintype "bidirectional"))
      (node (ref "U1") (pin "7") (pinfunction "6D_7") (pintype "input"))
      (node (ref "U2") (pin "7") (pinfunction "6D_7") (pintype "input"))
      (node (ref "U3") (pin "7") (pinfunction "6D_7") (pintype "input"))
      (node (ref "U4") (pin "7") (pinfunction "6D_7") (pintype "input"))
      (node (ref "U5") (pin "7") (pinfunction "6D_7") (pintype "input"))
      (node (ref "U6") (pin "7") (pinfunction "6D_7") (pintype "input"))
      (node (ref "U7") (pin "7") (pinfunction "6D_7") (pintype "input"))
      (node (ref "U8") (pin "7") (pinfunction "6D_7") (pintype "input"))
    )
    (net (code "16") (name "/D6") (class "Default")
      (node (ref "IC1") (pin "34") (pinfunction "(ADC6)PA6_34") (pintype "bidirectional"))
      (node (ref "U1") (pin "8") (pinfunction "7D_8") (pintype "input"))
      (node (ref "U2") (pin "8") (pinfunction "7D_8") (pintype "input"))
      (node (ref "U3") (pin "8") (pinfunction "7D_8") (pintype "input"))
      (node (ref "U4") (pin "8") (pinfunction "7D_8") (pintype "input"))
      (node (ref "U5") (pin "8") (pinfunction "7D_8") (pintype "input"))
      (node (ref "U6") (pin "8") (pinfunction "7D_8") (pintype "input"))
      (node (ref "U7") (pin "8") (pinfunction "7D_8") (pintype "input"))
      (node (ref "U8") (pin "8") (pinfunction "7D_8") (pintype "input"))
    )
    (net (code "17") (name "/D7") (class "Default")
      (node (ref "IC1") (pin "33") (pinfunction "(ADC7)PA7_33") (pintype "bidirectional"))
      (node (ref "U1") (pin "9") (pinfunction "8D_9") (pintype "input"))
      (node (ref "U2") (pin "9") (pinfunction "8D_9") (pintype "input"))
      (node (ref "U3") (pin "9") (pinfunction "8D_9") (pintype "input"))
      (node (ref "U4") (pin "9") (pinfunction "8D_9") (pintype "input"))
      (node (ref "U5") (pin "9") (pinfunction "8D_9") (pintype "input"))
      (node (ref "U6") (pin "9") (pinfunction "8D_9") (pintype "input"))
      (node (ref "U7") (pin "9") (pinfunction "8D_9") (pintype "input"))
      (node (ref "U8") (pin "9") (pinfunction "8D_9") (pintype "input"))
    )
    (net (code "18") (name "/OE") (class "Default")
      (node (ref "GPIO") (pin "1") (pinfunction "1_1") (pintype "passive"))
      (node (ref "IC1") (pin "21") (pinfunction "(OC2)PD7_21") (pintype "bidirectional"))
      (node (ref "U1") (pin "1") (pinfunction "~{OE}_1") (pintype "input"))
      (node (ref "U2") (pin "1") (pinfunction "~{OE}_1") (pintype "input"))
      (node (ref "U3") (pin "1") (pinfunction "~{OE}_1") (pintype "input"))
      (node (ref "U4") (pin "1") (pinfunction "~{OE}_1") (pintype "input"))
      (node (ref "U5") (pin "1") (pinfunction "~{OE}_1") (pintype "input"))
      (node (ref "U6") (pin "1") (pinfunction "~{OE}_1") (pintype "input"))
      (node (ref "U7") (pin "1") (pinfunction "~{OE}_1") (pintype "input"))
      (node (ref "U8") (pin "1") (pinfunction "~{OE}_1") (pintype "input"))
    )
    (net (code "19") (name "/PD2") (class "Default")
      (node (ref "GPIO") (pin "6") (pinfunction "6_6") (pintype "passive"))
      (node (ref "IC1") (pin "16") (pinfunction "(INT0)PD2_16") (pintype "bidirectional"))
    )
    (net (code "20") (name "/PD3") (class "Default")
      (node (ref "GPIO") (pin "5") (pinfunction "5_5") (pintype "passive"))
      (node (ref "IC1") (pin "17") (pinfunction "(INT1)PD3_17") (pintype "bidirectional"))
    )
    (net (code "21") (name "/PD4") (class "Default")
      (node (ref "GPIO") (pin "4") (pinfunction "4_4") (pintype "passive"))
      (node (ref "IC1") (pin "18") (pinfunction "(OC1B)PD4_18") (pintype "bidirectional"))
    )
    (net (code "22") (name "/PD5") (class "Default")
      (node (ref "GPIO") (pin "3") (pinfunction "3_3") (pintype "passive"))
      (node (ref "IC1") (pin "19") (pinfunction "(OC1A)PD5_19") (pintype "bidirectional"))
    )
    (net (code "23") (name "/PD6") (class "Default")
      (node (ref "D2") (pin "A") (pinfunction "A_A") (pintype "passive"))
      (node (ref "GPIO") (pin "2") (pinfunction "2_2") (pintype "passive"))
      (node (ref "IC1") (pin "20") (pinfunction "(ICP)PD6_20") (pintype "bidirectional"))
    )
    (net (code "24") (name "/RXD") (class "Default")
      (node (ref "GPIO") (pin "8") (pinfunction "8_8") (pintype "passive"))
      (node (ref "IC1") (pin "14") (pinfunction "(RXD)PD0_14") (pintype "bidirectional"))
    )
    (net (code "25") (name "/TXD") (class "Default")
      (node (ref "GPIO") (pin "7") (pinfunction "7_7") (pintype "passive"))
      (node (ref "IC1") (pin "15") (pinfunction "(TXD)PD1_15") (pintype "bidirectional"))
    )
    (net (code "26") (name "/VIN") (class "Default")
      (node (ref "POWER_IN") (pin "2") (pinfunction "2_2") (pintype "passive"))
      (node (ref "S1") (pin "1") (pinfunction "1_1") (pintype "passive"))
    )
    (net (code "27") (name "/XTAL1") (class "Default")
      (node (ref "C6") (pin "1") (pinfunction "1_1") (pintype "passive"))
      (node (ref "IC1") (pin "13") (pinfunction "XTAL1_13") (pintype "bidirectional"))
      (node (ref "Y1") (pin "1") (pinfunction "1_1") (pintype "passive"))
    )
    (net (code "28") (name "/XTAL2") (class "Default")
      (node (ref "C7") (pin "1") (pinfunction "1_1") (pintype "passive"))
      (node (ref "IC1") (pin "12") (pinfunction "XTAL2_12") (pintype "bidirectional"))
      (node (ref "Y1") (pin "2") (pinfunction "2_2") (pintype "passive"))
    )
    (net (code "30") (name "GND") (class "Default")
      (node (ref "AVRISP") (pin "10") (pinfunction "GND_10") (pintype "power_in"))
      (node (ref "AVRISP") (pin "4") (pinfunction "GND_4") (pintype "power_in"))
      (node (ref "AVRISP") (pin "6") (pinfunction "GND_6") (pintype "power_in"))
      (node (ref "AVRISP") (pin "8") (pinfunction "GND_8") (pintype "power_in"))
      (node (ref "C1") (pin "-") (pinfunction "-_-") (pintype "passive"))
      (node (ref "C10") (pin "1") (pinfunction "1_1") (pintype "passive"))
      (node (ref "C11") (pin "1") (pinfunction "1_1") (pintype "passive"))
      (node (ref "C12") (pin "1") (pinfunction "1_1") (pintype "passive"))
      (node (ref "C13") (pin "1") (pinfunction "1_1") (pintype "passive"))
      (node (ref "C14") (pin "1") (pinfunction "1_1") (pintype "passive"))
      (node (ref "C15") (pin "1") (pinfunction "1_1") (pintype "passive"))
      (node (ref "C2") (pin "2") (pinfunction "-_2") (pintype "passive"))
      (node (ref "C3") (pin "2") (pinfunction "-_2") (pintype "passive"))
      (node (ref "C4") (pin "2") (pinfunction "2_2") (pintype "passive"))
      (node (ref "C5") (pin "2") (pinfunction "2_2") (pintype "passive"))
      (node (ref "C6") (pin "2") (pinfunction "2_2") (pintype "passive"))
      (node (ref "C7") (pin "2") (pinfunction "2_2") (pintype "passive"))
      (node (ref "C8") (pin "1") (pinfunction "1_1") (pintype "passive"))
      (node (ref "C9") (pin "1") (pinfunction "1_1") (pintype "passive"))
      (node (ref "D1") (pin "C") (pinfunction "C_C") (pintype "passive"))
      (node (ref "IC1") (pin "11") (pinfunction "GND_11") (pintype "power_in"))
      (node (ref "IC1") (pin "31") (pinfunction "GND_31") (pintype "power_in"))
      (node (ref "POWER_IN") (pin "1") (pinfunction "1_1") (pintype "passive"))
      (node (ref "Q1") (pin "2") (pinfunction "E_2") (pintype "passive"))
      (node (ref "Q2") (pin "2") (pinfunction "E_2") (pintype "passive"))
      (node (ref "Q3") (pin "2") (pinfunction "E_2") (pintype "passive"))
      (node (ref "Q4") (pin "2") (pinfunction "E_2") (pintype "passive"))
      (node (ref "Q5") (pin "2") (pinfunction "E_2") (pintype "passive"))
      (node (ref "Q6") (pin "2") (pinfunction "E_2") (pintype "passive"))
      (node (ref "Q7") (pin "2") (pinfunction "E_2") (pintype "passive"))
      (node (ref "Q8") (pin "2") (pinfunction "E_2") (pintype "passive"))
      (node (ref "R66") (pin "P$1") (pinfunction "1_P$1") (pintype "passive"))
      (node (ref "S2") (pin "3") (pinfunction "2_3") (pintype "passive"))
      (node (ref "U1") (pin "10") (pinfunction "GND_10") (pintype "power_in"))
      (node (ref "U2") (pin "10") (pinfunction "GND_10") (pintype "power_in"))
      (node (ref "U3") (pin "10") (pinfunction "GND_10") (pintype "power_in"))
      (node (ref "U4") (pin "10") (pinfunction "GND_10") (pintype "power_in"))
      (node (ref "U5") (pin "10") (pinfunction "GND_10") (pintype "power_in"))
      (node (ref "U6") (pin "10") (pinfunction "GND_10") (pintype "power_in"))
      (node (ref "U7") (pin "10") (pinfunction "GND_10") (pintype "power_in"))
      (node (ref "U8") (pin "10") (pinfunction "GND_10") (pintype "power_in"))
    )
    (net (code "31") (name "Net-(AVRISP-MISO)") (class "Default")
      (node (ref "AVRISP") (pin "9") (pinfunction "MISO_9") (pintype "passive"))
      (node (ref "IC1") (pin "7") (pinfunction "(MISO)PB6_7") (pintype "bidirectional"))
      (node (ref "R76") (pin "P$1") (pinfunction "1_P$1") (pintype "passive"))
    )
    (net (code "32") (name "Net-(AVRISP-MOSI)") (class "Default")
      (node (ref "AVRISP") (pin "1") (pinfunction "MOSI_1") (pintype "passive"))
      (node (ref "IC1") (pin "6") (pinfunction "(MOSI)PB5_6") (pintype "bidirectional"))
      (node (ref "R77") (pin "P$1") (pinfunction "1_P$1") (pintype "passive"))
    )
    (net (code "33") (name "Net-(AVRISP-RESET)") (class "Default")
      (node (ref "AVRISP") (pin "5") (pinfunction "RESET_5") (pintype "passive"))
      (node (ref "IC1") (pin "9") (pinfunction "RESET_9") (pintype "input"))
      (node (ref "R83") (pin "P$1") (pinfunction "1_P$1") (pintype "passive"))
      (node (ref "S2") (pin "1") (pinfunction "1_1") (pintype "passive"))
    )
    (net (code "34") (name "Net-(AVRISP-SCK)") (class "Default")
      (node (ref "AVRISP") (pin "7") (pinfunction "SCK_7") (pintype "passive"))
      (node (ref "IC1") (pin "8") (pinfunction "(SCK)PB7_8") (pintype "bidirectional"))
      (node (ref "R75") (pin "P$1") (pinfunction "1_P$1") (pintype "passive"))
    )
    (net (code "35") (name "Net-(COL1-P)") (class "Default")
      (node (ref "COL1") (pin "1") (pinfunction "P_1") (pintype "passive"))
      (node (ref "R1") (pin "P$1") (pinfunction "1_P$1") (pintype "passive"))
    )
    (net (code "36") (name "Net-(COL2-P)") (class "Default")
      (node (ref "COL2") (pin "1") (pinfunction "P_1") (pintype "passive"))
      (node (ref "R2") (pin "P$1") (pinfunction "1_P$1") (pintype "passive"))
    )
    (net (code "37") (name "Net-(COL3-P)") (class "Default")
      (node (ref "COL3") (pin "1") (pinfunction "P_1") (pintype "passive"))
      (node (ref "R3") (pin "P$1") (pinfunction "1_P$1") (pintype "passive"))
    )
    (net (code "38") (name "Net-(COL4-P)") (class "Default")
      (node (ref "COL4") (pin "1") (pinfunction "P_1") (pintype "passive"))
      (node (ref "R4") (pin "P$1") (pinfunction "1_P$1") (pintype "passive"))
    )
    (net (code "39") (name "Net-(COL5-P)") (class "Default")
      (node (ref "COL5") (pin "1") (pinfunction "P_1") (pintype "passive"))
      (node (ref "R5") (pin "P$1") (pinfunction "1_P$1") (pintype "passive"))
    )
    (net (code "40") (name "Net-(COL6-P)") (class "Default")
      (node (ref "COL6") (pin "1") (pinfunction "P_1") (pintype "passive"))
      (node (ref "R6") (pin "P$1") (pinfunction "1_P$1") (pintype "passive"))
    )
    (net (code "41") (name "Net-(COL7-P)") (class "Default")
      (node (ref "COL7") (pin "1") (pinfunction "P_1") (pintype "passive"))
      (node (ref "R7") (pin "P$1") (pinfunction "1_P$1") (pintype "passive"))
    )
    (net (code "42") (name "Net-(COL8-P)") (class "Default")
      (node (ref "COL8") (pin "1") (pinfunction "P_1") (pintype "passive"))
      (node (ref "R8") (pin "P$1") (pinfunction "1_P$1") (pintype "passive"))
    )
    (net (code "43") (name "Net-(COL9-P)") (class "Default")
      (node (ref "COL9") (pin "1") (pinfunction "P_1") (pintype "passive"))
      (node (ref "R9") (pin "P$1") (pinfunction "1_P$1") (pintype "passive"))
    )
    (net (code "44") (name "Net-(COL10-P)") (class "Default")
      (node (ref "COL10") (pin "1") (pinfunction "P_1") (pintype "passive"))
      (node (ref "R10") (pin "P$1") (pinfunction "1_P$1") (pintype "passive"))
    )
    (net (code "45") (name "Net-(COL11-P)") (class "Default")
      (node (ref "COL11") (pin "1") (pinfunction "P_1") (pintype "passive"))
      (node (ref "R11") (pin "P$1") (pinfunction "1_P$1") (pintype "passive"))
    )
    (net (code "46") (name "Net-(COL12-P)") (class "Default")
      (node (ref "COL12") (pin "1") (pinfunction "P_1") (pintype "passive"))
      (node (ref "R12") (pin "P$1") (pinfunction "1_P$1") (pintype "passive"))
    )
    (net (code "47") (name "Net-(COL13-P)") (class "Default")
      (node (ref "COL13") (pin "1") (pinfunction "P_1") (pintype "passive"))
      (node (ref "R13") (pin "P$1") (pinfunction "1_P$1") (pintype "passive"))
    )
    (net (code "48") (name "Net-(COL14-P)") (class "Default")
      (node (ref "COL14") (pin "1") (pinfunction "P_1") (pintype "passive"))
      (node (ref "R14") (pin "P$1") (pinfunction "1_P$1") (pintype "passive"))
    )
    (net (code "49") (name "Net-(COL15-P)") (class "Default")
      (node (ref "COL15") (pin "1") (pinfunction "P_1") (pintype "passive"))
      (node (ref "R15") (pin "P$1") (pinfunction "1_P$1") (pintype "passive"))
    )
    (net (code "50") (name "Net-(COL16-P)") (class "Default")
      (node (ref "COL16") (pin "1") (pinfunction "P_1") (pintype "passive"))
      (node (ref "R16") (pin "P$1") (pinfunction "1_P$1") (pintype "passive"))
    )
    (net (code "51") (name "Net-(COL17-P)") (class "Default")
      (node (ref "COL17") (pin "1") (pinfunction "P_1") (pintype "passive"))
      (node (ref "R17") (pin "P$1") (pinfunction "1_P$1") (pintype "passive"))
    )
    (net (code "52") (name "Net-(COL18-P)") (class "Default")
      (node (ref "COL18") (pin "1") (pinfunction "P_1") (pintype "passive"))
      (node (ref "R18") (pin "P$1") (pinfunction "1_P$1") (pintype "passive"))
    )
    (net (code "53") (name "Net-(COL19-P)") (class "Default")
      (node (ref "COL19") (pin "1") (pinfunction "P_1") (pintype "passive"))
      (node (ref "R19") (pin "P$1") (pinfunction "1_P$1") (pintype "passive"))
    )
    (net (code "54") (name "Net-(COL20-P)") (class "Default")
      (node (ref "COL20") (pin "1") (pinfunction "P_1") (pintype "passive"))
      (node (ref "R20") (pin "P$1") (pinfunction "1_P$1") (pintype "passive"))
    )
    (net (code "55") (name "Net-(COL21-P)") (class "Default")
      (node (ref "COL21") (pin "1") (pinfunction "P_1") (pintype "passive"))
      (node (ref "R21") (pin "P$1") (pinfunction "1_P$1") (pintype "passive"))
    )
    (net (code "56") (name "Net-(COL22-P)") (class "Default")
      (node (ref "COL22") (pin "1") (pinfunction "P_1") (pintype "passive"))
      (node (ref "R22") (pin "P$1") (pinfunction "1_P$1") (pintype "passive"))
    )
    (net (code "57") (name "Net-(COL23-P)") (class "Default")
      (node (ref "COL23") (pin "1") (pinfunction "P_1") (pintype "passive"))
      (node (ref "R23") (pin "P$1") (pinfunction "1_P$1") (pintype "passive"))
    )
    (net (code "58") (name "Net-(COL24-P)") (class "Default")
      (node (ref "COL24") (pin "1") (pinfunction "P_1") (pintype "passive"))
      (node (ref "R24") (pin "P$1") (pinfunction "1_P$1") (pintype "passive"))
    )
    (net (code "59") (name "Net-(COL25-P)") (class "Default")
      (node (ref "COL25") (pin "1") (pinfunction "P_1") (pintype "passive"))
      (node (ref "R25") (pin "P$1") (pinfunction "1_P$1") (pintype "passive"))
    )
    (net (code "60") (name "Net-(COL26-P)") (class "Default")
      (node (ref "COL26") (pin "1") (pinfunction "P_1") (pintype "passive"))
      (node (ref "R26") (pin "P$1") (pinfunction "1_P$1") (pintype "passive"))
    )
    (net (code "61") (name "Net-(COL27-P)") (class "Default")
      (node (ref "COL27") (pin "1") (pinfunction "P_1") (pintype "passive"))
      (node (ref "R27") (pin "P$1") (pinfunction "1_P$1") (pintype "passive"))
    )
    (net (code "62") (name "Net-(COL28-P)") (class "Default")
      (node (ref "COL28") (pin "1") (pinfunction "P_1") (pintype "passive"))
      (node (ref "R28") (pin "P$1") (pinfunction "1_P$1") (pintype "passive"))
    )
    (net (code "63") (name "Net-(COL29-P)") (class "Default")
      (node (ref "COL29") (pin "1") (pinfunction "P_1") (pintype "passive"))
      (node (ref "R29") (pin "P$1") (pinfunction "1_P$1") (pintype "passive"))
    )
    (net (code "64") (name "Net-(COL30-P)") (class "Default")
      (node (ref "COL30") (pin "1") (pinfunction "P_1") (pintype "passive"))
      (node (ref "R30") (pin "P$1") (pinfunction "1_P$1") (pintype "passive"))
    )
    (net (code "65") (name "Net-(COL31-P)") (class "Default")
      (node (ref "COL31") (pin "1") (pinfunction "P_1") (pintype "passive"))
      (node (ref "R31") (pin "P$1") (pinfunction "1_P$1") (pintype "passive"))
    )
    (net (code "66") (name "Net-(COL32-P)") (class "Default")
      (node (ref "COL32") (pin "1") (pinfunction "P_1") (pintype "passive"))
      (node (ref "R32") (pin "P$1") (pinfunction "1_P$1") (pintype "passive"))
    )
    (net (code "67") (name "Net-(COL33-P)") (class "Default")
      (node (ref "COL33") (pin "1") (pinfunction "P_1") (pintype "passive"))
      (node (ref "R33") (pin "P$1") (pinfunction "1_P$1") (pintype "passive"))
    )
    (net (code "68") (name "Net-(COL34-P)") (class "Default")
      (node (ref "COL34") (pin "1") (pinfunction "P_1") (pintype "passive"))
      (node (ref "R34") (pin "P$1") (pinfunction "1_P$1") (pintype "passive"))
    )
    (net (code "69") (name "Net-(COL35-P)") (class "Default")
      (node (ref "COL35") (pin "1") (pinfunction "P_1") (pintype "passive"))
      (node (ref "R35") (pin "P$1") (pinfunction "1_P$1") (pintype "passive"))
    )
    (net (code "70") (name "Net-(COL36-P)") (class "Default")
      (node (ref "COL36") (pin "1") (pinfunction "P_1") (pintype "passive"))
      (node (ref "R36") (pin "P$1") (pinfunction "1_P$1") (pintype "passive"))
    )
    (net (code "71") (name "Net-(COL37-P)") (class "Default")
      (node (ref "COL37") (pin "1") (pinfunction "P_1") (pintype "passive"))
      (node (ref "R37") (pin "P$1") (pinfunction "1_P$1") (pintype "passive"))
    )
    (net (code "72") (name "Net-(COL38-P)") (class "Default")
      (node (ref "COL38") (pin "1") (pinfunction "P_1") (pintype "passive"))
      (node (ref "R38") (pin "P$1") (pinfunction "1_P$1") (pintype "passive"))
    )
    (net (code "73") (name "Net-(COL39-P)") (class "Default")
      (node (ref "COL39") (pin "1") (pinfunction "P_1") (pintype "passive"))
      (node (ref "R39") (pin "P$1") (pinfunction "1_P$1") (pintype "passive"))
    )
    (net (code "74") (name "Net-(COL40-P)") (class "Default")
      (node (ref "COL40") (pin "1") (pinfunction "P_1") (pintype "passive"))
      (node (ref "R40") (pin "P$1") (pinfunction "1_P$1") (pintype "passive"))
    )
    (net (code "75") (name "Net-(COL41-P)") (class "Default")
      (node (ref "COL41") (pin "1") (pinfunction "P_1") (pintype "passive"))
      (node (ref "R41") (pin "P$1") (pinfunction "1_P$1") (pintype "passive"))
    )
    (net (code "76") (name "Net-(COL42-P)") (class "Default")
      (node (ref "COL42") (pin "1") (pinfunction "P_1") (pintype "passive"))
      (node (ref "R42") (pin "P$1") (pinfunction "1_P$1") (pintype "passive"))
    )
    (net (code "77") (name "Net-(COL43-P)") (class "Default")
      (node (ref "COL43") (pin "1") (pinfunction "P_1") (pintype "passive"))
      (node (ref "R43") (pin "P$1") (pinfunction "1_P$1") (pintype "passive"))
    )
    (net (code "78") (name "Net-(COL44-P)") (class "Default")
      (node (ref "COL44") (pin "1") (pinfunction "P_1") (pintype "passive"))
      (node (ref "R44") (pin "P$1") (pinfunction "1_P$1") (pintype "passive"))
    )
    (net (code "79") (name "Net-(COL45-P)") (class "Default")
      (node (ref "COL45") (pin "1") (pinfunction "P_1") (pintype "passive"))
      (node (ref "R45") (pin "P$1") (pinfunction "1_P$1") (pintype "passive"))
    )
    (net (code "80") (name "Net-(COL46-P)") (class "Default")
      (node (ref "COL46") (pin "1") (pinfunction "P_1") (pintype "passive"))
      (node (ref "R46") (pin "P$1") (pinfunction "1_P$1") (pintype "passive"))
    )
    (net (code "81") (name "Net-(COL47-P)") (class "Default")
      (node (ref "COL47") (pin "1") (pinfunction "P_1") (pintype "passive"))
      (node (ref "R47") (pin "P$1") (pinfunction "1_P$1") (pintype "passive"))
    )
    (net (code "82") (name "Net-(COL48-P)") (class "Default")
      (node (ref "COL48") (pin "1") (pinfunction "P_1") (pintype "passive"))
      (node (ref "R48") (pin "P$1") (pinfunction "1_P$1") (pintype "passive"))
    )
    (net (code "83") (name "Net-(COL49-P)") (class "Default")
      (node (ref "COL49") (pin "1") (pinfunction "P_1") (pintype "passive"))
      (node (ref "R49") (pin "P$1") (pinfunction "1_P$1") (pintype "passive"))
    )
    (net (code "84") (name "Net-(COL50-P)") (class "Default")
      (node (ref "COL50") (pin "1") (pinfunction "P_1") (pintype "passive"))
      (node (ref "R50") (pin "P$1") (pinfunction "1_P$1") (pintype "passive"))
    )
    (net (code "85") (name "Net-(COL51-P)") (class "Default")
      (node (ref "COL51") (pin "1") (pinfunction "P_1") (pintype "passive"))
      (node (ref "R51") (pin "P$1") (pinfunction "1_P$1") (pintype "passive"))
    )
    (net (code "86") (name "Net-(COL52-P)") (class "Default")
      (node (ref "COL52") (pin "1") (pinfunction "P_1") (pintype "passive"))
      (node (ref "R52") (pin "P$1") (pinfunction "1_P$1") (pintype "passive"))
    )
    (net (code "87") (name "Net-(COL53-P)") (class "Default")
      (node (ref "COL53") (pin "1") (pinfunction "P_1") (pintype "passive"))
      (node (ref "R53") (pin "P$1") (pinfunction "1_P$1") (pintype "passive"))
    )
    (net (code "88") (name "Net-(COL54-P)") (class "Default")
      (node (ref "COL54") (pin "1") (pinfunction "P_1") (pintype "passive"))
      (node (ref "R54") (pin "P$1") (pinfunction "1_P$1") (pintype "passive"))
    )
    (net (code "89") (name "Net-(COL55-P)") (class "Default")
      (node (ref "COL55") (pin "1") (pinfunction "P_1") (pintype "passive"))
      (node (ref "R55") (pin "P$1") (pinfunction "1_P$1") (pintype "passive"))
    )
    (net (code "90") (name "Net-(COL56-P)") (class "Default")
      (node (ref "COL56") (pin "1") (pinfunction "P_1") (pintype "passive"))
      (node (ref "R56") (pin "P$1") (pinfunction "1_P$1") (pintype "passive"))
    )
    (net (code "91") (name "Net-(COL57-P)") (class "Default")
      (node (ref "COL57") (pin "1") (pinfunction "P_1") (pintype "passive"))
      (node (ref "R57") (pin "P$1") (pinfunction "1_P$1") (pintype "passive"))
    )
    (net (code "92") (name "Net-(COL58-P)") (class "Default")
      (node (ref "COL58") (pin "1") (pinfunction "P_1") (pintype "passive"))
      (node (ref "R58") (pin "P$1") (pinfunction "1_P$1") (pintype "passive"))
    )
    (net (code "93") (name "Net-(COL59-P)") (class "Default")
      (node (ref "COL59") (pin "1") (pinfunction "P_1") (pintype "passive"))
      (node (ref "R59") (pin "P$1") (pinfunction "1_P$1") (pintype "passive"))
    )
    (net (code "94") (name "Net-(COL60-P)") (class "Default")
      (node (ref "COL60") (pin "1") (pinfunction "P_1") (pintype "passive"))
      (node (ref "R60") (pin "P$1") (pinfunction "1_P$1") (pintype "passive"))
    )
    (net (code "95") (name "Net-(COL61-P)") (class "Default")
      (node (ref "COL61") (pin "1") (pinfunction "P_1") (pintype "passive"))
      (node (ref "R61") (pin "P$1") (pinfunction "1_P$1") (pintype "passive"))
    )
    (net (code "96") (name "Net-(COL62-P)") (class "Default")
      (node (ref "COL62") (pin "1") (pinfunction "P_1") (pintype "passive"))
      (node (ref "R62") (pin "P$1") (pinfunction "1_P$1") (pintype "passive"))
    )
    (net (code "97") (name "Net-(COL63-P)") (class "Default")
      (node (ref "COL63") (pin "1") (pinfunction "P_1") (pintype "passive"))
      (node (ref "R63") (pin "P$1") (pinfunction "1_P$1") (pintype "passive"))
    )
    (net (code "98") (name "Net-(COL64-P)") (class "Default")
      (node (ref "COL64") (pin "1") (pinfunction "P_1") (pintype "passive"))
      (node (ref "R64") (pin "P$1") (pinfunction "1_P$1") (pintype "passive"))
    )
    (net (code "99") (name "Net-(IC1-(AIN0{slash}INT2)PB2)") (class "Default")
      (node (ref "IC1") (pin "3") (pinfunction "(AIN0/INT2)PB2_3") (pintype "bidirectional"))
      (node (ref "R80") (pin "P$1") (pinfunction "1_P$1") (pintype "passive"))
    )
    (net (code "100") (name "Net-(IC1-(AIN1{slash}OC0)PB3)") (class "Default")
      (node (ref "IC1") (pin "4") (pinfunction "(AIN1/OC0)PB3_4") (pintype "bidirectional"))
      (node (ref "R79") (pin "P$1") (pinfunction "1_P$1") (pintype "passive"))
    )
    (net (code "101") (name "Net-(IC1-(SS)PB4)") (class "Default")
      (node (ref "IC1") (pin "5") (pinfunction "(SS)PB4_5") (pintype "bidirectional"))
      (node (ref "R78") (pin "P$1") (pinfunction "1_P$1") (pintype "passive"))
    )
    (net (code "102") (name "Net-(IC1-(T0{slash}XCK)PB0)") (class "Default")
      (node (ref "IC1") (pin "1") (pinfunction "(T0/XCK)PB0_1") (pintype "bidirectional"))
      (node (ref "R82") (pin "P$1") (pinfunction "1_P$1") (pintype "passive"))
    )
    (net (code "103") (name "Net-(IC1-(T1)PB1)") (class "Default")
      (node (ref "IC1") (pin "2") (pinfunction "(T1)PB1_2") (pintype "bidirectional"))
      (node (ref "R81") (pin "P$1") (pinfunction "1_P$1") (pintype "passive"))
    )
    (net (code "104") (name "Net-(Q1-B)") (class "Default")
      (node (ref "Q1") (pin "1") (pinfunction "B_1") (pintype "passive"))
      (node (ref "R82") (pin "P$2") (pinfunction "2_P$2") (pintype "passive"))
    )
    (net (code "105") (name "Net-(Q1-C)") (class "Default")
      (node (ref "LED_C") (pin "1") (pinfunction "1_1") (pintype "passive"))
      (node (ref "Q1") (pin "3") (pinfunction "C_3") (pintype "passive"))
      (node (ref "R67") (pin "P$1") (pinfunction "1_P$1") (pintype "passive"))
    )
    (net (code "106") (name "Net-(Q2-B)") (class "Default")
      (node (ref "Q2") (pin "1") (pinfunction "B_1") (pintype "passive"))
      (node (ref "R81") (pin "P$2") (pinfunction "2_P$2") (pintype "passive"))
    )
    (net (code "107") (name "Net-(Q2-C)") (class "Default")
      (node (ref "LED_C") (pin "2") (pinfunction "2_2") (pintype "passive"))
      (node (ref "Q2") (pin "3") (pinfunction "C_3") (pintype "passive"))
      (node (ref "R68") (pin "P$1") (pinfunction "1_P$1") (pintype "passive"))
    )
    (net (code "108") (name "Net-(Q3-B)") (class "Default")
      (node (ref "Q3") (pin "1") (pinfunction "B_1") (pintype "passive"))
      (node (ref "R80") (pin "P$2") (pinfunction "2_P$2") (pintype "passive"))
    )
    (net (code "109") (name "Net-(Q3-C)") (class "Default")
      (node (ref "LED_C") (pin "3") (pinfunction "3_3") (pintype "passive"))
      (node (ref "Q3") (pin "3") (pinfunction "C_3") (pintype "passive"))
      (node (ref "R69") (pin "P$1") (pinfunction "1_P$1") (pintype "passive"))
    )
    (net (code "110") (name "Net-(Q4-B)") (class "Default")
      (node (ref "Q4") (pin "1") (pinfunction "B_1") (pintype "passive"))
      (node (ref "R79") (pin "P$2") (pinfunction "2_P$2") (pintype "passive"))
    )
    (net (code "111") (name "Net-(Q4-C)") (class "Default")
      (node (ref "LED_C") (pin "4") (pinfunction "4_4") (pintype "passive"))
      (node (ref "Q4") (pin "3") (pinfunction "C_3") (pintype "passive"))
      (node (ref "R70") (pin "P$1") (pinfunction "1_P$1") (pintype "passive"))
    )
    (net (code "112") (name "Net-(Q5-B)") (class "Default")
      (node (ref "Q5") (pin "1") (pinfunction "B_1") (pintype "passive"))
      (node (ref "R78") (pin "P$2") (pinfunction "2_P$2") (pintype "passive"))
    )
    (net (code "113") (name "Net-(Q5-C)") (class "Default")
      (node (ref "LED_C") (pin "5") (pinfunction "5_5") (pintype "passive"))
      (node (ref "Q5") (pin "3") (pinfunction "C_3") (pintype "passive"))
      (node (ref "R71") (pin "P$1") (pinfunction "1_P$1") (pintype "passive"))
    )
    (net (code "114") (name "Net-(Q6-B)") (class "Default")
      (node (ref "Q6") (pin "1") (pinfunction "B_1") (pintype "passive"))
      (node (ref "R77") (pin "P$2") (pinfunction "2_P$2") (pintype "passive"))
    )
    (net (code "115") (name "Net-(Q6-C)") (class "Default")
      (node (ref "LED_C") (pin "6") (pinfunction "6_6") (pintype "passive"))
      (node (ref "Q6") (pin "3") (pinfunction "C_3") (pintype "passive"))
      (node (ref "R72") (pin "P$1") (pinfunction "1_P$1") (pintype "passive"))
    )
    (net (code "116") (name "Net-(Q7-B)") (class "Default")
      (node (ref "Q7") (pin "1") (pinfunction "B_1") (pintype "passive"))
      (node (ref "R76") (pin "P$2") (pinfunction "2_P$2") (pintype "passive"))
    )
    (net (code "117") (name "Net-(Q7-C)") (class "Default")
      (node (ref "LED_C") (pin "7") (pinfunction "7_7") (pintype "passive"))
      (node (ref "Q7") (pin "3") (pinfunction "C_3") (pintype "passive"))
      (node (ref "R73") (pin "P$1") (pinfunction "1_P$1") (pintype "passive"))
    )
    (net (code "118") (name "Net-(Q8-B)") (class "Default")
      (node (ref "Q8") (pin "1") (pinfunction "B_1") (pintype "passive"))
      (node (ref "R75") (pin "P$2") (pinfunction "2_P$2") (pintype "passive"))
    )
    (net (code "119") (name "Net-(Q8-C)") (class "Default")
      (node (ref "LED_C") (pin "8") (pinfunction "8_8") (pintype "passive"))
      (node (ref "Q8") (pin "3") (pinfunction "C_3") (pintype "passive"))
      (node (ref "R74") (pin "P$1") (pinfunction "1_P$1") (pintype "passive"))
    )
    (net (code "120") (name "Net-(R1-2)") (class "Default")
      (node (ref "R1") (pin "P$2") (pinfunction "2_P$2") (pintype "passive"))
      (node (ref "U8") (pin "19") (pinfunction "1Q_19") (pintype "output"))
    )
    (net (code "121") (name "Net-(R2-2)") (class "Default")
      (node (ref "R2") (pin "P$2") (pinfunction "2_P$2") (pintype "passive"))
      (node (ref "U8") (pin "18") (pinfunction "2Q_18") (pintype "output"))
    )
    (net (code "122") (name "Net-(R3-2)") (class "Default")
      (node (ref "R3") (pin "P$2") (pinfunction "2_P$2") (pintype "passive"))
      (node (ref "U8") (pin "17") (pinfunction "3Q_17") (pintype "output"))
    )
    (net (code "123") (name "Net-(R4-2)") (class "Default")
      (node (ref "R4") (pin "P$2") (pinfunction "2_P$2") (pintype "passive"))
      (node (ref "U8") (pin "16") (pinfunction "4Q_16") (pintype "output"))
    )
    (net (code "124") (name "Net-(R5-2)") (class "Default")
      (node (ref "R5") (pin "P$2") (pinfunction "2_P$2") (pintype "passive"))
      (node (ref "U8") (pin "15") (pinfunction "5Q_15") (pintype "output"))
    )
    (net (code "125") (name "Net-(R6-2)") (class "Default")
      (node (ref "R6") (pin "P$2") (pinfunction "2_P$2") (pintype "passive"))
      (node (ref "U8") (pin "14") (pinfunction "6Q_14") (pintype "output"))
    )
    (net (code "126") (name "Net-(R7-2)") (class "Default")
      (node (ref "R7") (pin "P$2") (pinfunction "2_P$2") (pintype "passive"))
      (node (ref "U8") (pin "13") (pinfunction "7Q_13") (pintype "output"))
    )
    (net (code "127") (name "Net-(R8-2)") (class "Default")
      (node (ref "R8") (pin "P$2") (pinfunction "2_P$2") (pintype "passive"))
      (node (ref "U8") (pin "12") (pinfunction "8Q_12") (pintype "output"))
    )
    (net (code "128") (name "Net-(R9-2)") (class "Default")
      (node (ref "R9") (pin "P$2") (pinfunction "2_P$2") (pintype "passive"))
      (node (ref "U1") (pin "19") (pinfunction "1Q_19") (pintype "output"))
    )
    (net (code "129") (name "Net-(R10-2)") (class "Default")
      (node (ref "R10") (pin "P$2") (pinfunction "2_P$2") (pintype "passive"))
      (node (ref "U1") (pin "18") (pinfunction "2Q_18") (pintype "output"))
    )
    (net (code "130") (name "Net-(R11-2)") (class "Default")
      (node (ref "R11") (pin "P$2") (pinfunction "2_P$2") (pintype "passive"))
      (node (ref "U1") (pin "17") (pinfunction "3Q_17") (pintype "output"))
    )
    (net (code "131") (name "Net-(R12-2)") (class "Default")
      (node (ref "R12") (pin "P$2") (pinfunction "2_P$2") (pintype "passive"))
      (node (ref "U1") (pin "16") (pinfunction "4Q_16") (pintype "output"))
    )
    (net (code "132") (name "Net-(R13-2)") (class "Default")
      (node (ref "R13") (pin "P$2") (pinfunction "2_P$2") (pintype "passive"))
      (node (ref "U1") (pin "15") (pinfunction "5Q_15") (pintype "output"))
    )
    (net (code "133") (name "Net-(R14-2)") (class "Default")
      (node (ref "R14") (pin "P$2") (pinfunction "2_P$2") (pintype "passive"))
      (node (ref "U1") (pin "14") (pinfunction "6Q_14") (pintype "output"))
    )
    (net (code "134") (name "Net-(R15-2)") (class "Default")
      (node (ref "R15") (pin "P$2") (pinfunction "2_P$2") (pintype "passive"))
      (node (ref "U1") (pin "13") (pinfunction "7Q_13") (pintype "output"))
    )
    (net (code "135") (name "Net-(R16-2)") (class "Default")
      (node (ref "R16") (pin "P$2") (pinfunction "2_P$2") (pintype "passive"))
      (node (ref "U1") (pin "12") (pinfunction "8Q_12") (pintype "output"))
    )
    (net (code "136") (name "Net-(R17-2)") (class "Default")
      (node (ref "R17") (pin "P$2") (pinfunction "2_P$2") (pintype "passive"))
      (node (ref "U2") (pin "19") (pinfunction "1Q_19") (pintype "output"))
    )
    (net (code "137") (name "Net-(R18-2)") (class "Default")
      (node (ref "R18") (pin "P$2") (pinfunction "2_P$2") (pintype "passive"))
      (node (ref "U2") (pin "18") (pinfunction "2Q_18") (pintype "output"))
    )
    (net (code "138") (name "Net-(R19-2)") (class "Default")
      (node (ref "R19") (pin "P$2") (pinfunction "2_P$2") (pintype "passive"))
      (node (ref "U2") (pin "17") (pinfunction "3Q_17") (pintype "output"))
    )
    (net (code "139") (name "Net-(R20-2)") (class "Default")
      (node (ref "R20") (pin "P$2") (pinfunction "2_P$2") (pintype "passive"))
      (node (ref "U2") (pin "16") (pinfunction "4Q_16") (pintype "output"))
    )
    (net (code "140") (name "Net-(R21-2)") (class "Default")
      (node (ref "R21") (pin "P$2") (pinfunction "2_P$2") (pintype "passive"))
      (node (ref "U2") (pin "15") (pinfunction "5Q_15") (pintype "output"))
    )
    (net (code "141") (name "Net-(R22-2)") (class "Default")
      (node (ref "R22") (pin "P$2") (pinfunction "2_P$2") (pintype "passive"))
      (node (ref "U2") (pin "14") (pinfunction "6Q_14") (pintype "output"))
    )
    (net (code "142") (name "Net-(R23-2)") (class "Default")
      (node (ref "R23") (pin "P$2") (pinfunction "2_P$2") (pintype "passive"))
      (node (ref "U2") (pin "13") (pinfunction "7Q_13") (pintype "output"))
    )
    (net (code "143") (name "Net-(R24-2)") (class "Default")
      (node (ref "R24") (pin "P$2") (pinfunction "2_P$2") (pintype "passive"))
      (node (ref "U2") (pin "12") (pinfunction "8Q_12") (pintype "output"))
    )
    (net (code "144") (name "Net-(R25-2)") (class "Default")
      (node (ref "R25") (pin "P$2") (pinfunction "2_P$2") (pintype "passive"))
      (node (ref "U3") (pin "19") (pinfunction "1Q_19") (pintype "output"))
    )
    (net (code "145") (name "Net-(R26-2)") (class "Default")
      (node (ref "R26") (pin "P$2") (pinfunction "2_P$2") (pintype "passive"))
      (node (ref "U3") (pin "18") (pinfunction "2Q_18") (pintype "output"))
    )
    (net (code "146") (name "Net-(R27-2)") (class "Default")
      (node (ref "R27") (pin "P$2") (pinfunction "2_P$2") (pintype "passive"))
      (node (ref "U3") (pin "17") (pinfunction "3Q_17") (pintype "output"))
    )
    (net (code "147") (name "Net-(R28-2)") (class "Default")
      (node (ref "R28") (pin "P$2") (pinfunction "2_P$2") (pintype "passive"))
      (node (ref "U3") (pin "16") (pinfunction "4Q_16") (pintype "output"))
    )
    (net (code "148") (name "Net-(R29-2)") (class "Default")
      (node (ref "R29") (pin "P$2") (pinfunction "2_P$2") (pintype "passive"))
      (node (ref "U3") (pin "15") (pinfunction "5Q_15") (pintype "output"))
    )
    (net (code "149") (name "Net-(R30-2)") (class "Default")
      (node (ref "R30") (pin "P$2") (pinfunction "2_P$2") (pintype "passive"))
      (node (ref "U3") (pin "14") (pinfunction "6Q_14") (pintype "output"))
    )
    (net (code "150") (name "Net-(R31-2)") (class "Default")
      (node (ref "R31") (pin "P$2") (pinfunction "2_P$2") (pintype "passive"))
      (node (ref "U3") (pin "13") (pinfunction "7Q_13") (pintype "output"))
    )
    (net (code "151") (name "Net-(R32-2)") (class "Default")
      (node (ref "R32") (pin "P$2") (pinfunction "2_P$2") (pintype "passive"))
      (node (ref "U3") (pin "12") (pinfunction "8Q_12") (pintype "output"))
    )
    (net (code "152") (name "Net-(R33-2)") (class "Default")
      (node (ref "R33") (pin "P$2") (pinfunction "2_P$2") (pintype "passive"))
      (node (ref "U4") (pin "19") (pinfunction "1Q_19") (pintype "output"))
    )
    (net (code "153") (name "Net-(R34-2)") (class "Default")
      (node (ref "R34") (pin "P$2") (pinfunction "2_P$2") (pintype "passive"))
      (node (ref "U4") (pin "18") (pinfunction "2Q_18") (pintype "output"))
    )
    (net (code "154") (name "Net-(R35-2)") (class "Default")
      (node (ref "R35") (pin "P$2") (pinfunction "2_P$2") (pintype "passive"))
      (node (ref "U4") (pin "17") (pinfunction "3Q_17") (pintype "output"))
    )
    (net (code "155") (name "Net-(R36-2)") (class "Default")
      (node (ref "R36") (pin "P$2") (pinfunction "2_P$2") (pintype "passive"))
      (node (ref "U4") (pin "16") (pinfunction "4Q_16") (pintype "output"))
    )
    (net (code "156") (name "Net-(R37-2)") (class "Default")
      (node (ref "R37") (pin "P$2") (pinfunction "2_P$2") (pintype "passive"))
      (node (ref "U4") (pin "15") (pinfunction "5Q_15") (pintype "output"))
    )
    (net (code "157") (name "Net-(R38-2)") (class "Default")
      (node (ref "R38") (pin "P$2") (pinfunction "2_P$2") (pintype "passive"))
      (node (ref "U4") (pin "14") (pinfunction "6Q_14") (pintype "output"))
    )
    (net (code "158") (name "Net-(R39-2)") (class "Default")
      (node (ref "R39") (pin "P$2") (pinfunction "2_P$2") (pintype "passive"))
      (node (ref "U4") (pin "13") (pinfunction "7Q_13") (pintype "output"))
    )
    (net (code "159") (name "Net-(R40-2)") (class "Default")
      (node (ref "R40") (pin "P$2") (pinfunction "2_P$2") (pintype "passive"))
      (node (ref "U4") (pin "12") (pinfunction "8Q_12") (pintype "output"))
    )
    (net (code "160") (name "Net-(R41-2)") (class "Default")
      (node (ref "R41") (pin "P$2") (pinfunction "2_P$2") (pintype "passive"))
      (node (ref "U5") (pin "19") (pinfunction "1Q_19") (pintype "output"))
    )
    (net (code "161") (name "Net-(R42-2)") (class "Default")
      (node (ref "R42") (pin "P$2") (pinfunction "2_P$2") (pintype "passive"))
      (node (ref "U5") (pin "18") (pinfunction "2Q_18") (pintype "output"))
    )
    (net (code "162") (name "Net-(R43-2)") (class "Default")
      (node (ref "R43") (pin "P$2") (pinfunction "2_P$2") (pintype "passive"))
      (node (ref "U5") (pin "17") (pinfunction "3Q_17") (pintype "output"))
    )
    (net (code "163") (name "Net-(R44-2)") (class "Default")
      (node (ref "R44") (pin "P$2") (pinfunction "2_P$2") (pintype "passive"))
      (node (ref "U5") (pin "16") (pinfunction "4Q_16") (pintype "output"))
    )
    (net (code "164") (name "Net-(R45-2)") (class "Default")
      (node (ref "R45") (pin "P$2") (pinfunction "2_P$2") (pintype "passive"))
      (node (ref "U5") (pin "15") (pinfunction "5Q_15") (pintype "output"))
    )
    (net (code "165") (name "Net-(R46-2)") (class "Default")
      (node (ref "R46") (pin "P$2") (pinfunction "2_P$2") (pintype "passive"))
      (node (ref "U5") (pin "14") (pinfunction "6Q_14") (pintype "output"))
    )
    (net (code "166") (name "Net-(R47-2)") (class "Default")
      (node (ref "R47") (pin "P$2") (pinfunction "2_P$2") (pintype "passive"))
      (node (ref "U5") (pin "13") (pinfunction "7Q_13") (pintype "output"))
    )
    (net (code "167") (name "Net-(R48-2)") (class "Default")
      (node (ref "R48") (pin "P$2") (pinfunction "2_P$2") (pintype "passive"))
      (node (ref "U5") (pin "12") (pinfunction "8Q_12") (pintype "output"))
    )
    (net (code "168") (name "Net-(R49-2)") (class "Default")
      (node (ref "R49") (pin "P$2") (pinfunction "2_P$2") (pintype "passive"))
      (node (ref "U6") (pin "19") (pinfunction "1Q_19") (pintype "output"))
    )
    (net (code "169") (name "Net-(R50-2)") (class "Default")
      (node (ref "R50") (pin "P$2") (pinfunction "2_P$2") (pintype "passive"))
      (node (ref "U6") (pin "18") (pinfunction "2Q_18") (pintype "output"))
    )
    (net (code "170") (name "Net-(R51-2)") (class "Default")
      (node (ref "R51") (pin "P$2") (pinfunction "2_P$2") (pintype "passive"))
      (node (ref "U6") (pin "17") (pinfunction "3Q_17") (pintype "output"))
    )
    (net (code "171") (name "Net-(R52-2)") (class "Default")
      (node (ref "R52") (pin "P$2") (pinfunction "2_P$2") (pintype "passive"))
      (node (ref "U6") (pin "16") (pinfunction "4Q_16") (pintype "output"))
    )
    (net (code "172") (name "Net-(R53-2)") (class "Default")
      (node (ref "R53") (pin "P$2") (pinfunction "2_P$2") (pintype "passive"))
      (node (ref "U6") (pin "15") (pinfunction "5Q_15") (pintype "output"))
    )
    (net (code "173") (name "Net-(R54-2)") (class "Default")
      (node (ref "R54") (pin "P$2") (pinfunction "2_P$2") (pintype "passive"))
      (node (ref "U6") (pin "14") (pinfunction "6Q_14") (pintype "output"))
    )
    (net (code "174") (name "Net-(R55-2)") (class "Default")
      (node (ref "R55") (pin "P$2") (pinfunction "2_P$2") (pintype "passive"))
      (node (ref "U6") (pin "13") (pinfunction "7Q_13") (pintype "output"))
    )
    (net (code "175") (name "Net-(R56-2)") (class "Default")
      (node (ref "R56") (pin "P$2") (pinfunction "2_P$2") (pintype "passive"))
      (node (ref "U6") (pin "12") (pinfunction "8Q_12") (pintype "output"))
    )
    (net (code "176") (name "Net-(R57-2)") (class "Default")
      (node (ref "R57") (pin "P$2") (pinfunction "2_P$2") (pintype "passive"))
      (node (ref "U7") (pin "19") (pinfunction "1Q_19") (pintype "output"))
    )
    (net (code "177") (name "Net-(R58-2)") (class "Default")
      (node (ref "R58") (pin "P$2") (pinfunction "2_P$2") (pintype "passive"))
      (node (ref "U7") (pin "18") (pinfunction "2Q_18") (pintype "output"))
    )
    (net (code "178") (name "Net-(R59-2)") (class "Default")
      (node (ref "R59") (pin "P$2") (pinfunction "2_P$2") (pintype "passive"))
      (node (ref "U7") (pin "17") (pinfunction "3Q_17") (pintype "output"))
    )
    (net (code "179") (name "Net-(R60-2)") (class "Default")
      (node (ref "R60") (pin "P$2") (pinfunction "2_P$2") (pintype "passive"))
      (node (ref "U7") (pin "16") (pinfunction "4Q_16") (pintype "output"))
    )
    (net (code "180") (name "Net-(R61-2)") (class "Default")
      (node (ref "R61") (pin "P$2") (pinfunction "2_P$2") (pintype "passive"))
      (node (ref "U7") (pin "15") (pinfunction "5Q_15") (pintype "output"))
    )
    (net (code "181") (name "Net-(R62-2)") (class "Default")
      (node (ref "R62") (pin "P$2") (pinfunction "2_P$2") (pintype "passive"))
      (node (ref "U7") (pin "14") (pinfunction "6Q_14") (pintype "output"))
    )
    (net (code "182") (name "Net-(R63-2)") (class "Default")
      (node (ref "R63") (pin "P$2") (pinfunction "2_P$2") (pintype "passive"))
      (node (ref "U7") (pin "13") (pinfunction "7Q_13") (pintype "output"))
    )
    (net (code "183") (name "Net-(R64-2)") (class "Default")
      (node (ref "R64") (pin "P$2") (pinfunction "2_P$2") (pintype "passive"))
      (node (ref "U7") (pin "12") (pinfunction "8Q_12") (pintype "output"))
    )
    (net (code "184") (name "Net-(R65-1)") (class "Default")
      (node (ref "D1") (pin "A") (pinfunction "A_A") (pintype "passive"))
      (node (ref "R65") (pin "P$1") (pinfunction "1_P$1") (pintype "passive"))
    )
    (net (code "185") (name "Net-(R66-2)") (class "Default")
      (node (ref "D2") (pin "C") (pinfunction "C_C") (pintype "passive"))
      (node (ref "R66") (pin "P$2") (pinfunction "2_P$2") (pintype "passive"))
    )
    (net (code "186") (name "VCC") (class "Default")
      (node (ref "AVRISP") (pin "2") (pinfunction "VCC_2") (pintype "power_in"))
      (node (ref "C1") (pin "+") (pinfunction "+_+") (pintype "passive"))
      (node (ref "C10") (pin "2") (pinfunction "2_2") (pintype "passive"))
      (node (ref "C11") (pin "2") (pinfunction "2_2") (pintype "passive"))
      (node (ref "C12") (pin "2") (pinfunction "2_2") (pintype "passive"))
      (node (ref "C13") (pin "2") (pinfunction "2_2") (pintype "passive"))
      (node (ref "C14") (pin "2") (pinfunction "2_2") (pintype "passive"))
      (node (ref "C15") (pin "2") (pinfunction "2_2") (pintype "passive"))
      (node (ref "C2") (pin "1") (pinfunction "+_1") (pintype "passive"))
      (node (ref "C3") (pin "1") (pinfunction "+_1") (pintype "passive"))
      (node (ref "C4") (pin "1") (pinfunction "1_1") (pintype "passive"))
      (node (ref "C5") (pin "1") (pinfunction "1_1") (pintype "passive"))
      (node (ref "C8") (pin "2") (pinfunction "2_2") (pintype "passive"))
      (node (ref "C9") (pin "2") (pinfunction "2_2") (pintype "passive"))
      (node (ref "IC1") (pin "10") (pinfunction "VCC_10") (pintype "power_in"))
      (node (ref "IC1") (pin "30") (pinfunction "AVCC_30") (pintype "power_in"))
      (node (ref "IC1") (pin "32") (pinfunction "AREF_32") (pintype "passive"))
      (node (ref "R65") (pin "P$2") (pinfunction "2_P$2") (pintype "passive"))
      (node (ref "R67") (pin "P$2") (pinfunction "2_P$2") (pintype "passive"))
      (node (ref "R68") (pin "P$2") (pinfunction "2_P$2") (pintype "passive"))
      (node (ref "R69") (pin "P$2") (pinfunction "2_P$2") (pintype "passive"))
      (node (ref "R70") (pin "P$2") (pinfunction "2_P$2") (pintype "passive"))
      (node (ref "R71") (pin "P$2") (pinfunction "2_P$2") (pintype "passive"))
      (node (ref "R72") (pin "P$2") (pinfunction "2_P$2") (pintype "passive"))
      (node (ref "R73") (pin "P$2") (pinfunction "2_P$2") (pintype "passive"))
      (node (ref "R74") (pin "P$2") (pinfunction "2_P$2") (pintype "passive"))
      (node (ref "R83") (pin "P$2") (pinfunction "2_P$2") (pintype "passive"))
      (node (ref "S1") (pin "2") (pinfunction "2_2") (pintype "passive"))
      (node (ref "U1") (pin "20") (pinfunction "VCC_20") (pintype "power_in"))
      (node (ref "U2") (pin "20") (pinfunction "VCC_20") (pintype "power_in"))
      (node (ref "U3") (pin "20") (pinfunction "VCC_20") (pintype "power_in"))
      (node (ref "U4") (pin "20") (pinfunction "VCC_20") (pintype "power_in"))
      (node (ref "U5") (pin "20") (pinfunction "VCC_20") (pintype "power_in"))
      (node (ref "U6") (pin "20") (pinfunction "VCC_20") (pintype "power_in"))
      (node (ref "U7") (pin "20") (pinfunction "VCC_20") (pintype "power_in"))
      (node (ref "U8") (pin "20") (pinfunction "VCC_20") (pintype "power_in"))
    )
    (net (code "187") (name "unconnected-(AVRISP-NC-Pad3)") (class "Default")
      (node (ref "AVRISP") (pin "3") (pinfunction "NC_3") (pintype "no_connect"))
    )
  )
)
